# raijel_sim_v1.net
KiCad netlist of a schematic drawn in Altium Designer
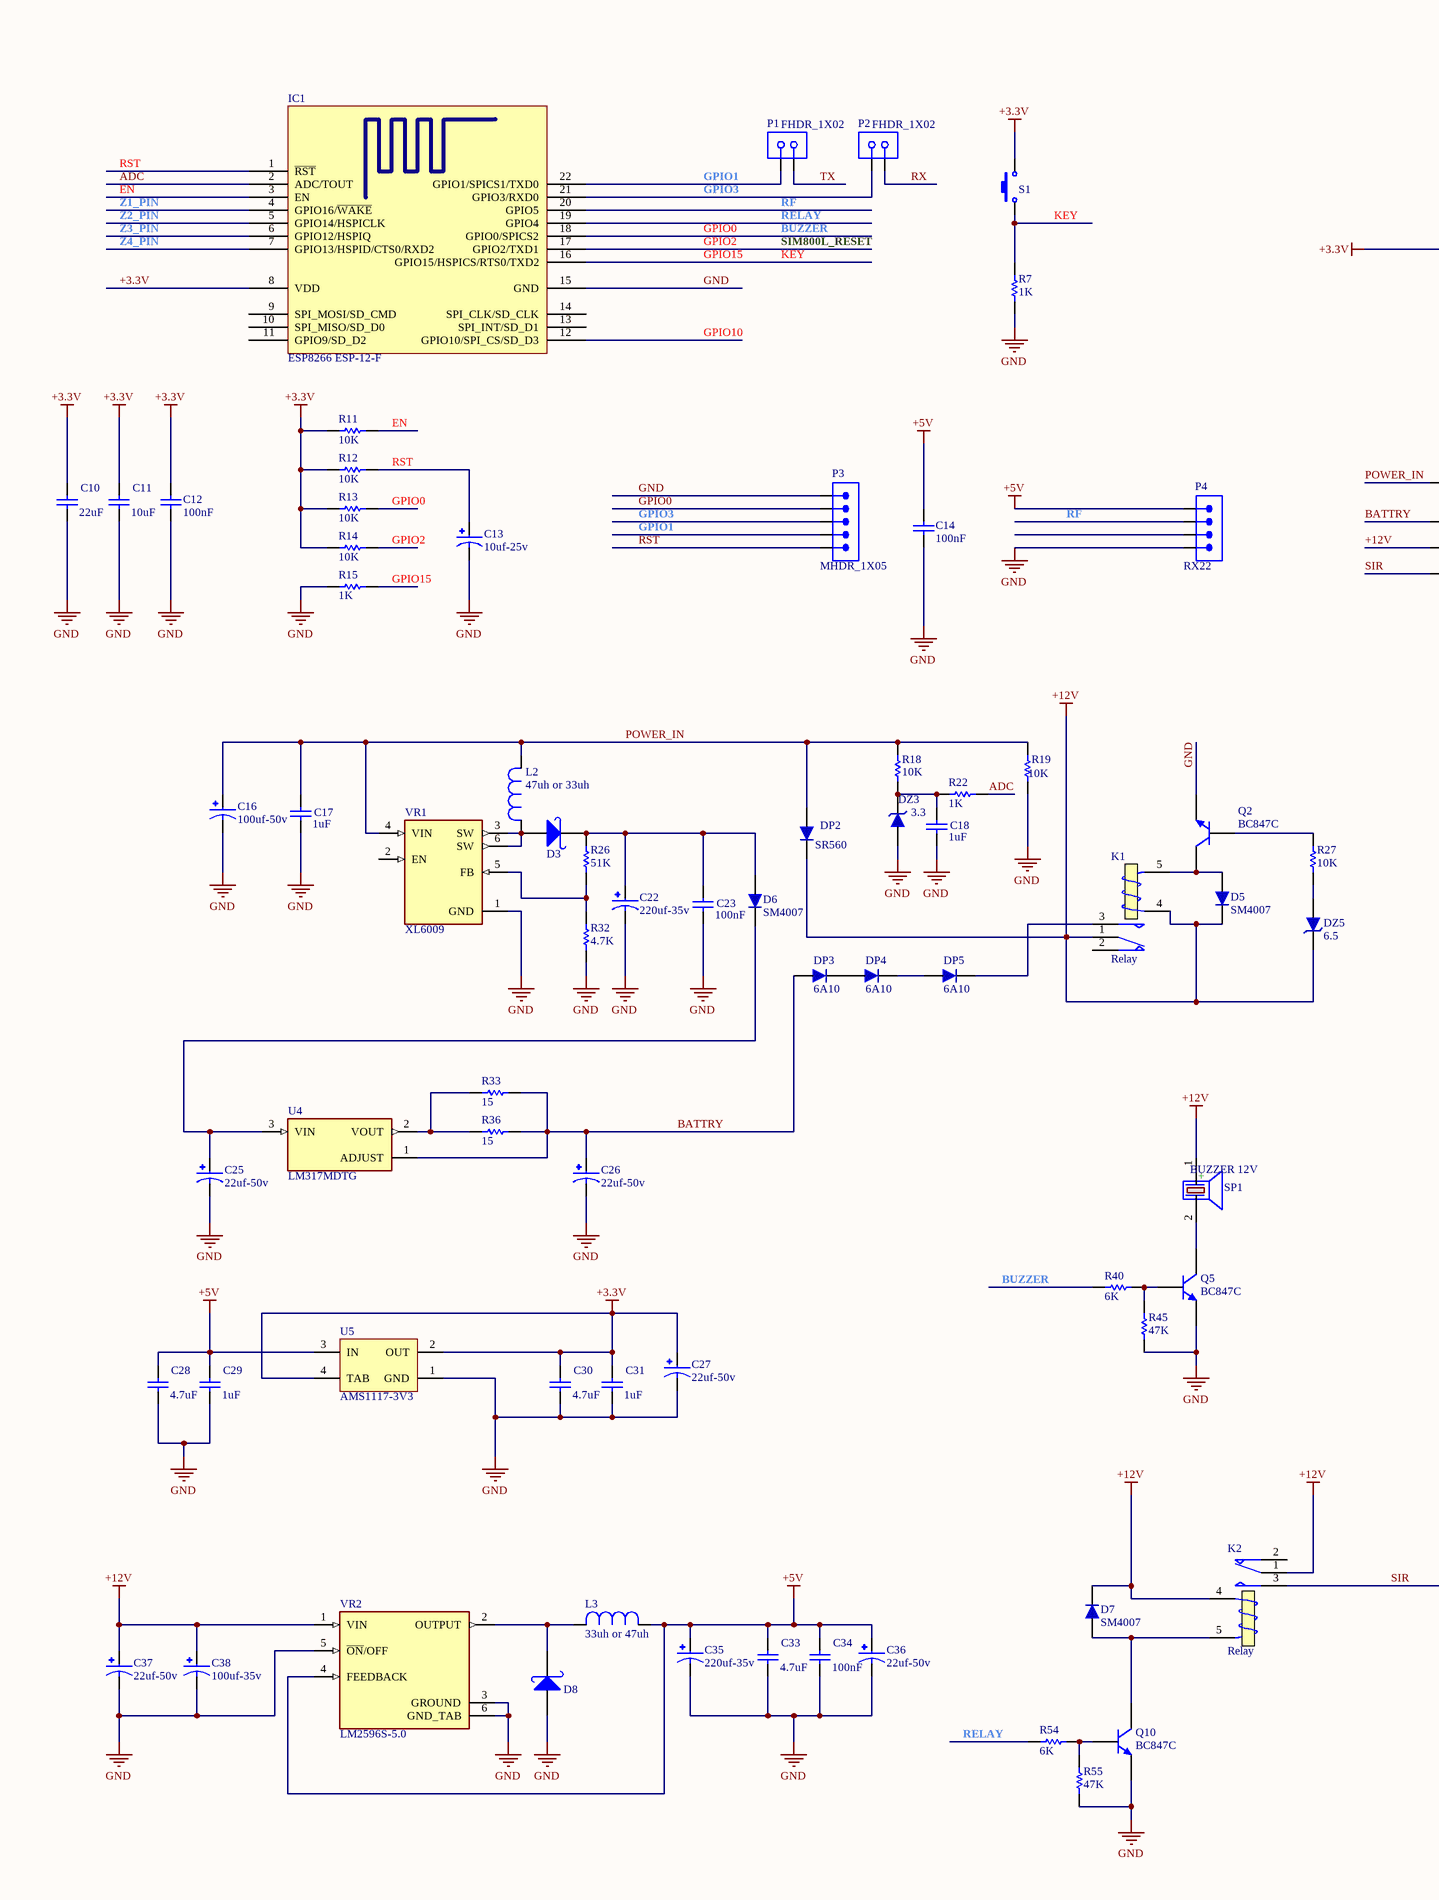
[diagram p0: raijel_sim_v1.SchDoc, left]
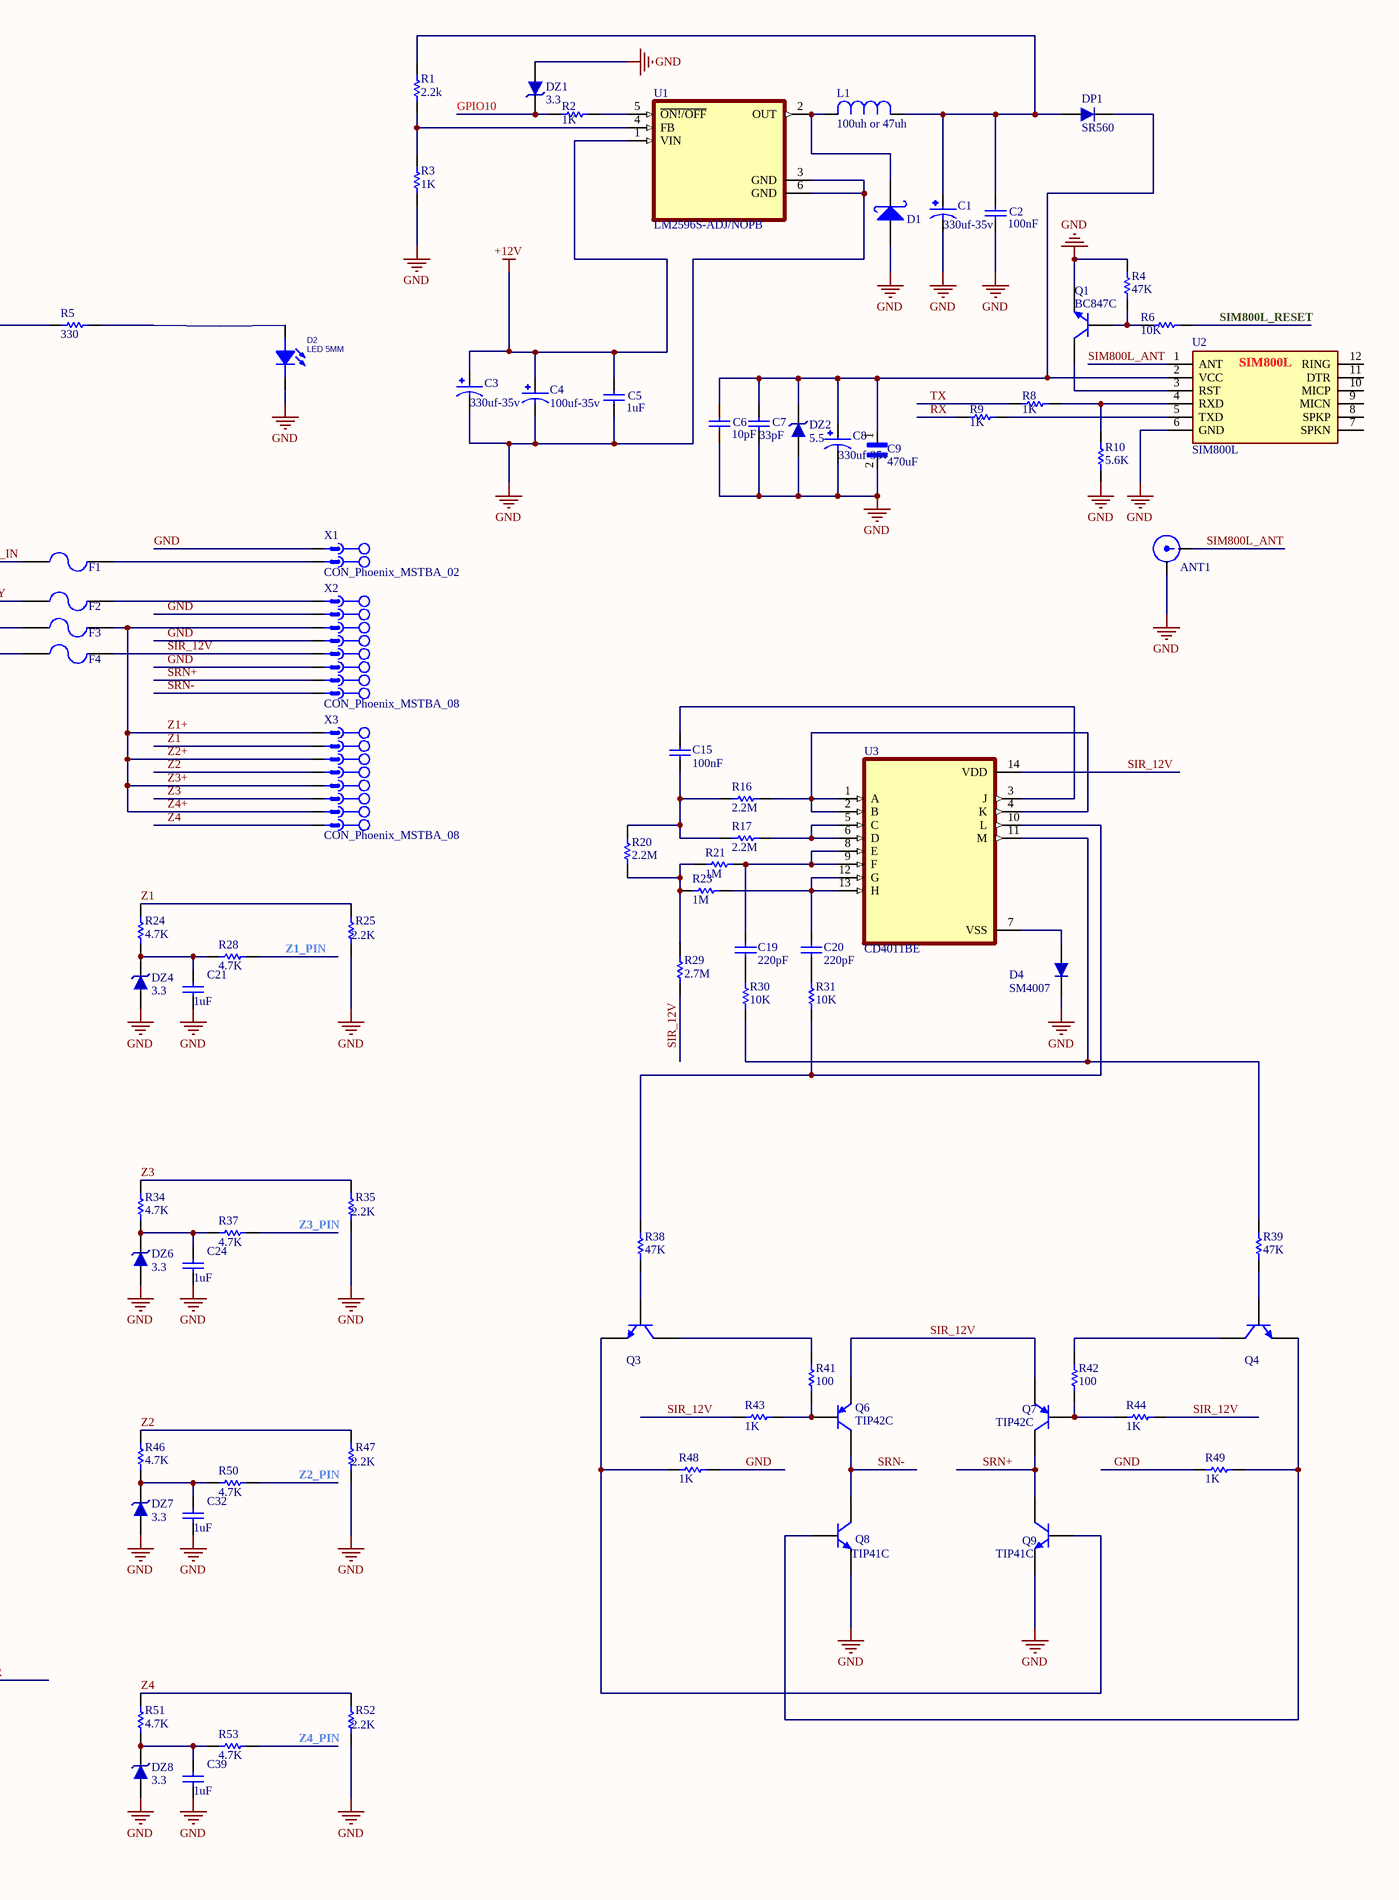
[diagram p1: raijel_sim_v1.SchDoc, right]

(export (version "E")
  (design (tool "Eeschema 10.0.6"))
  (components
    (comp (ref "ANT1")
      (value "Antenna")
      (footprint "SMA")
      (fields (field (name "DESIGNER") "Ali Hafizi"))
      (libsource (lib "Altium") (part "ANT SMA"))
    )
    (comp (ref "C1")
      (value "330uf-35v")
      (footprint "CAP_EEEFP1V221AV")
      (description "CAP ALUM 220UF 20% 35V SMD")
      (fields (field (name "MF") "Panasonic Electronic Components") (field (name "MP") "EEE-FP1V221AV"))
      (libsource (lib "EEEFP1V221AV-220-35v") (part "EEEFP1V221AV"))
    )
    (comp (ref "C2")
      (value "100nF")
      (footprint "CAP0805")
      (description "TOTAL CAPACITOR SMD PACK")
      (fields (field (name "DESIGNER") "Abbas Basereh"))
      (libsource (lib "Altium") (part "CAP SMD PACKAGE"))
    )
    (comp (ref "C3")
      (value "330uf-35v")
      (footprint "CAP_EEEFP1V221AV")
      (description "CAP ALUM 220UF 20% 35V SMD")
      (fields (field (name "MF") "Panasonic Electronic Components") (field (name "MP") "EEE-FP1V221AV"))
      (libsource (lib "EEEFP1V221AV-220-35v") (part "EEEFP1V221AV"))
    )
    (comp (ref "C4")
      (value "100uf-35v")
      (footprint "CAP_EEEFP1V221AV")
      (description "CAP ALUM 220UF 20% 35V SMD")
      (fields (field (name "MF") "Panasonic Electronic Components") (field (name "MP") "EEE-FP1V221AV"))
      (libsource (lib "EEEFP1V221AV-220-35v") (part "EEEFP1V221AV"))
    )
    (comp (ref "C5")
      (value "1uF")
      (footprint "CAP0805")
      (description "TOTAL CAPACITOR SMD PACK")
      (fields (field (name "DESIGNER") "Abbas Basereh"))
      (libsource (lib "Altium") (part "CAP SMD PACKAGE"))
    )
    (comp (ref "C6")
      (value "10pF")
      (footprint "CAP0805")
      (description "TOTAL CAPACITOR SMD PACK")
      (fields (field (name "DESIGNER") "Abbas Basereh"))
      (libsource (lib "Altium") (part "CAP SMD PACKAGE"))
    )
    (comp (ref "C7")
      (value "33pF")
      (footprint "CAP0805")
      (description "TOTAL CAPACITOR SMD PACK")
      (fields (field (name "DESIGNER") "Abbas Basereh"))
      (libsource (lib "Altium") (part "CAP SMD PACKAGE"))
    )
    (comp (ref "C8")
      (value "330uf-35v")
      (footprint "CAP_EEEFP1V221AV")
      (description "CAP ALUM 220UF 20% 35V SMD")
      (fields (field (name "MF") "Panasonic Electronic Components") (field (name "MP") "EEE-FP1V221AV"))
      (libsource (lib "EEEFP1V221AV-220-35v") (part "EEEFP1V221AV"))
    )
    (comp (ref "C9")
      (value "470uF")
      (footprint "CAPPM7343X310N")
      (description "TC 47uF 25V 10% Case D")
      (fields (field (name "MP") "TAJD476K025RNJ"))
      (libsource (lib "TAJD476K025RNJ") (part "TAJD476K025RNJ"))
    )
    (comp (ref "C10")
      (value "22uF")
      (footprint "CAP0805")
      (description "TOTAL CAPACITOR SMD PACK")
      (fields (field (name "DESIGNER") "Abbas Basereh"))
      (libsource (lib "Altium") (part "CAP SMD PACKAGE"))
    )
    (comp (ref "C11")
      (value "10uF")
      (footprint "CAP0805")
      (description "TOTAL CAPACITOR SMD PACK")
      (fields (field (name "DESIGNER") "Abbas Basereh"))
      (libsource (lib "Altium") (part "CAP SMD PACKAGE"))
    )
    (comp (ref "C12")
      (value "100nF")
      (footprint "CAP0805")
      (description "TOTAL CAPACITOR SMD PACK")
      (fields (field (name "DESIGNER") "Abbas Basereh"))
      (libsource (lib "Altium") (part "CAP SMD PACKAGE"))
    )
    (comp (ref "C13")
      (value "10uf-25v")
      (footprint "CAP_EEEFN1H220UR")
      (description "CAP ALUM 22UF 20% 50V SMD")
      (fields (field (name "MF") "Panasonic Electronic Components") (field (name "MP") "EEE-FN1H220UR"))
      (libsource (lib "EEEFN1H220UR_22uf-50v") (part "EEEFN1H220UR"))
    )
    (comp (ref "C14")
      (value "100nF")
      (footprint "CAP0805")
      (description "TOTAL CAPACITOR SMD PACK")
      (fields (field (name "DESIGNER") "Abbas Basereh"))
      (libsource (lib "Altium") (part "CAP SMD PACKAGE"))
    )
    (comp (ref "C15")
      (value "100nF")
      (footprint "CAP Ceramic 5mm")
      (description "CAP Ceramic Total")
      (fields (field (name "DESIGNER") "Ali Hafizi"))
      (libsource (lib "Altium") (part "CAP CERAMIC TOTAL SIZE"))
    )
    (comp (ref "C16")
      (value "100uf-50v")
      (footprint "CAP_EEEFN1H101L")
      (description "CAP ALUM 100UF 20% 50V SMD")
      (fields (field (name "MP") "EEE-FN1H101L") (field (name "MF") "Panasonic Electronic Components"))
      (libsource (lib "EEEFN1H101L-100-50v") (part "EEEFN1H101L"))
    )
    (comp (ref "C17")
      (value "1uF")
      (footprint "CAP0805")
      (description "TOTAL CAPACITOR SMD PACK")
      (fields (field (name "DESIGNER") "Abbas Basereh"))
      (libsource (lib "Altium") (part "CAP SMD PACKAGE"))
    )
    (comp (ref "C18")
      (value "1uF")
      (footprint "CAP0805")
      (description "TOTAL CAPACITOR SMD PACK")
      (fields (field (name "DESIGNER") "Abbas Basereh"))
      (libsource (lib "Altium") (part "CAP SMD PACKAGE"))
    )
    (comp (ref "C19")
      (value "220pF")
      (footprint "CAP Ceramic 5mm")
      (description "CAP Ceramic Total")
      (fields (field (name "DESIGNER") "Ali Hafizi"))
      (libsource (lib "Altium") (part "CAP CERAMIC TOTAL SIZE"))
    )
    (comp (ref "C20")
      (value "220pF")
      (footprint "CAP Ceramic 5mm")
      (description "CAP Ceramic Total")
      (fields (field (name "DESIGNER") "Ali Hafizi"))
      (libsource (lib "Altium") (part "CAP CERAMIC TOTAL SIZE"))
    )
    (comp (ref "C21")
      (value "1uF")
      (footprint "CAP0805")
      (description "TOTAL CAPACITOR SMD PACK")
      (fields (field (name "DESIGNER") "Abbas Basereh"))
      (libsource (lib "Altium") (part "CAP SMD PACKAGE"))
    )
    (comp (ref "C22")
      (value "220uf-35v")
      (footprint "CAP_EEEFP1V221AV")
      (description "CAP ALUM 220UF 20% 35V SMD")
      (fields (field (name "MF") "Panasonic Electronic Components") (field (name "MP") "EEE-FP1V221AV"))
      (libsource (lib "EEEFP1V221AV-220-35v") (part "EEEFP1V221AV"))
    )
    (comp (ref "C23")
      (value "100nF")
      (footprint "CAP0805")
      (description "TOTAL CAPACITOR SMD PACK")
      (fields (field (name "DESIGNER") "Abbas Basereh"))
      (libsource (lib "Altium") (part "CAP SMD PACKAGE"))
    )
    (comp (ref "C24")
      (value "1uF")
      (footprint "CAP0805")
      (description "TOTAL CAPACITOR SMD PACK")
      (fields (field (name "DESIGNER") "Abbas Basereh"))
      (libsource (lib "Altium") (part "CAP SMD PACKAGE"))
    )
    (comp (ref "C25")
      (value "22uf-50v")
      (footprint "CAP_EEEFN1H220UR")
      (description "CAP ALUM 22UF 20% 50V SMD")
      (fields (field (name "MF") "Panasonic Electronic Components") (field (name "MP") "EEE-FN1H220UR"))
      (libsource (lib "EEEFN1H220UR_22uf-50v") (part "EEEFN1H220UR"))
    )
    (comp (ref "C26")
      (value "22uf-50v")
      (footprint "CAP_EEEFN1H220UR")
      (description "CAP ALUM 22UF 20% 50V SMD")
      (fields (field (name "MF") "Panasonic Electronic Components") (field (name "MP") "EEE-FN1H220UR"))
      (libsource (lib "EEEFN1H220UR_22uf-50v") (part "EEEFN1H220UR"))
    )
    (comp (ref "C27")
      (value "22uf-50v")
      (footprint "CAP_EEEFN1H220UR")
      (description "CAP ALUM 22UF 20% 50V SMD")
      (fields (field (name "MF") "Panasonic Electronic Components") (field (name "MP") "EEE-FN1H220UR"))
      (libsource (lib "EEEFN1H220UR_22uf-50v") (part "EEEFN1H220UR"))
    )
    (comp (ref "C28")
      (value "4.7uF")
      (footprint "CAP0805")
      (description "TOTAL CAPACITOR SMD PACK")
      (fields (field (name "DESIGNER") "Abbas Basereh"))
      (libsource (lib "Altium") (part "CAP SMD PACKAGE"))
    )
    (comp (ref "C29")
      (value "1uF")
      (footprint "CAP0805")
      (description "TOTAL CAPACITOR SMD PACK")
      (fields (field (name "DESIGNER") "Abbas Basereh"))
      (libsource (lib "Altium") (part "CAP SMD PACKAGE"))
    )
    (comp (ref "C30")
      (value "4.7uF")
      (footprint "CAP0805")
      (description "TOTAL CAPACITOR SMD PACK")
      (fields (field (name "DESIGNER") "Abbas Basereh"))
      (libsource (lib "Altium") (part "CAP SMD PACKAGE"))
    )
    (comp (ref "C31")
      (value "1uF")
      (footprint "CAP0805")
      (description "TOTAL CAPACITOR SMD PACK")
      (fields (field (name "DESIGNER") "Abbas Basereh"))
      (libsource (lib "Altium") (part "CAP SMD PACKAGE"))
    )
    (comp (ref "C32")
      (value "1uF")
      (footprint "CAP0805")
      (description "TOTAL CAPACITOR SMD PACK")
      (fields (field (name "DESIGNER") "Abbas Basereh"))
      (libsource (lib "Altium") (part "CAP SMD PACKAGE"))
    )
    (comp (ref "C33")
      (value "4.7uF")
      (footprint "CAP0805")
      (description "TOTAL CAPACITOR SMD PACK")
      (fields (field (name "DESIGNER") "Abbas Basereh"))
      (libsource (lib "Altium") (part "CAP SMD PACKAGE"))
    )
    (comp (ref "C34")
      (value "100nF")
      (footprint "CAP0805")
      (description "TOTAL CAPACITOR SMD PACK")
      (fields (field (name "DESIGNER") "Abbas Basereh"))
      (libsource (lib "Altium") (part "CAP SMD PACKAGE"))
    )
    (comp (ref "C35")
      (value "220uf-35v")
      (footprint "CAP_EEEFP1V221AV")
      (description "CAP ALUM 220UF 20% 35V SMD")
      (fields (field (name "MF") "Panasonic Electronic Components") (field (name "MP") "EEE-FP1V221AV"))
      (libsource (lib "EEEFP1V221AV-220-35v") (part "EEEFP1V221AV"))
    )
    (comp (ref "C36")
      (value "22uf-50v")
      (footprint "CAP_EEEFN1H220UR")
      (description "CAP ALUM 22UF 20% 50V SMD")
      (fields (field (name "MF") "Panasonic Electronic Components") (field (name "MP") "EEE-FN1H220UR"))
      (libsource (lib "EEEFN1H220UR_22uf-50v") (part "EEEFN1H220UR"))
    )
    (comp (ref "C37")
      (value "22uf-50v")
      (footprint "CAP_EEEFN1H220UR")
      (description "CAP ALUM 22UF 20% 50V SMD")
      (fields (field (name "MF") "Panasonic Electronic Components") (field (name "MP") "EEE-FN1H220UR"))
      (libsource (lib "EEEFN1H220UR_22uf-50v") (part "EEEFN1H220UR"))
    )
    (comp (ref "C38")
      (value "100uf-35v")
      (footprint "CAP_EEEFP1V221AV")
      (description "CAP ALUM 220UF 20% 35V SMD")
      (fields (field (name "MF") "Panasonic Electronic Components") (field (name "MP") "EEE-FP1V221AV"))
      (libsource (lib "EEEFP1V221AV-220-35v") (part "EEEFP1V221AV"))
    )
    (comp (ref "C39")
      (value "1uF")
      (footprint "CAP0805")
      (description "TOTAL CAPACITOR SMD PACK")
      (fields (field (name "DESIGNER") "Abbas Basereh"))
      (libsource (lib "Altium") (part "CAP SMD PACKAGE"))
    )
    (comp (ref "D1")
      (value "1n5822")
      (footprint "DO-214AB(SMC)")
      (description "Schottky Rectifiers")
      (fields
        (field (name "MANUFACTURER") "ON Semiconductor/Fairchild")
        (field (name "DESIGNER") "Abbas Basereh")
      )
      (libsource (lib "Altium") (part "1N5822 SMD"))
    )
    (comp (ref "D2")
      (value "LED 5MM")
      (footprint "LED5MM_GRN")
      (description "Light Emitting Diode")
      (fields (field (name "DESIGNER") "Abbas Basereh"))
      (libsource (lib "Altium") (part "LED 5MM"))
    )
    (comp (ref "D3")
      (value "1n5822")
      (footprint "DO-214AB(SMC)")
      (description "Schottky Rectifiers")
      (fields
        (field (name "MANUFACTURER") "ON Semiconductor/Fairchild")
        (field (name "DESIGNER") "Abbas Basereh")
      )
      (libsource (lib "Altium") (part "1N5822 SMD"))
    )
    (comp (ref "D4")
      (value "SM4007")
      (footprint "DIODE SMD")
      (description "Diode SMD Pakage")
      (libsource (lib "Altium") (part "Diode SMD Package"))
    )
    (comp (ref "D5")
      (value "SM4007")
      (footprint "DIODE SMD")
      (description "Diode SMD Pakage")
      (libsource (lib "Altium") (part "Diode SMD Package"))
    )
    (comp (ref "D6")
      (value "SM4007")
      (footprint "DIODE SMD")
      (description "Diode SMD Pakage")
      (libsource (lib "Altium") (part "Diode SMD Package"))
    )
    (comp (ref "D7")
      (value "SM4007")
      (footprint "DIODE SMD")
      (description "Diode SMD Pakage")
      (libsource (lib "Altium") (part "Diode SMD Package"))
    )
    (comp (ref "D8")
      (value "1n5822")
      (footprint "DO-214AB(SMC)")
      (description "Schottky Rectifiers")
      (fields
        (field (name "MANUFACTURER") "ON Semiconductor/Fairchild")
        (field (name "DESIGNER") "Abbas Basereh")
      )
      (libsource (lib "Altium") (part "1N5822 SMD"))
    )
    (comp (ref "DP1")
      (value "SR560")
      (footprint "DO-201AD - vertical")
      (description "General Semiconductor. Revision 3A 1000V Silicon Rectifier")
      (fields (field (name "DESIGNER") "Abbas Basereh"))
      (libsource (lib "General 1") (part "1N5408 3A 1000V"))
    )
    (comp (ref "DP2")
      (value "SR560")
      (footprint "DO-201AD - vertical")
      (description "General Semiconductor. Revision 3A 1000V Silicon Rectifier")
      (fields (field (name "DESIGNER") "Abbas Basereh"))
      (libsource (lib "General 1") (part "1N5408 3A 1000V"))
    )
    (comp (ref "DP3")
      (value "6A10")
      (footprint "DO-201AD - vertical")
      (description "General Semiconductor. Revision 3A 1000V Silicon Rectifier")
      (fields (field (name "DESIGNER") "Abbas Basereh"))
      (libsource (lib "General 1") (part "1N5408 3A 1000V"))
    )
    (comp (ref "DP4")
      (value "6A10")
      (footprint "DO-201AD - vertical")
      (description "General Semiconductor. Revision 3A 1000V Silicon Rectifier")
      (fields (field (name "DESIGNER") "Abbas Basereh"))
      (libsource (lib "General 1") (part "1N5408 3A 1000V"))
    )
    (comp (ref "DP5")
      (value "6A10")
      (footprint "DO-201AD - vertical")
      (description "General Semiconductor. Revision 3A 1000V Silicon Rectifier")
      (fields (field (name "DESIGNER") "Abbas Basereh"))
      (libsource (lib "General 1") (part "1N5408 3A 1000V"))
    )
    (comp (ref "DZ1")
      (value "3.3")
      (footprint "SOD80, LL-34")
      (description "DIODE ZENER GENERAL")
      (fields (field (name "PUBLISHER") "Abbas Basereh"))
      (libsource (lib "Altium") (part "ZENER GENERAL DIODE"))
    )
    (comp (ref "DZ2")
      (value "5.5")
      (footprint "SOD80, LL-34")
      (description "DIODE ZENER GENERAL")
      (fields (field (name "PUBLISHER") "Abbas Basereh"))
      (libsource (lib "Altium") (part "ZENER GENERAL DIODE"))
    )
    (comp (ref "DZ3")
      (value "3.3")
      (footprint "SOD80, LL-34")
      (description "DIODE ZENER GENERAL")
      (fields (field (name "PUBLISHER") "Abbas Basereh"))
      (libsource (lib "Altium") (part "ZENER GENERAL DIODE"))
    )
    (comp (ref "DZ4")
      (value "3.3")
      (footprint "SOD80, LL-34")
      (description "DIODE ZENER GENERAL")
      (fields (field (name "PUBLISHER") "Abbas Basereh"))
      (libsource (lib "Altium") (part "ZENER GENERAL DIODE"))
    )
    (comp (ref "DZ5")
      (value "6.5")
      (footprint "SOD80, LL-34")
      (description "DIODE ZENER GENERAL")
      (fields (field (name "PUBLISHER") "Abbas Basereh"))
      (libsource (lib "Altium") (part "ZENER GENERAL DIODE"))
    )
    (comp (ref "DZ6")
      (value "3.3")
      (footprint "SOD80, LL-34")
      (description "DIODE ZENER GENERAL")
      (fields (field (name "PUBLISHER") "Abbas Basereh"))
      (libsource (lib "Altium") (part "ZENER GENERAL DIODE"))
    )
    (comp (ref "DZ7")
      (value "3.3")
      (footprint "SOD80, LL-34")
      (description "DIODE ZENER GENERAL")
      (fields (field (name "PUBLISHER") "Abbas Basereh"))
      (libsource (lib "Altium") (part "ZENER GENERAL DIODE"))
    )
    (comp (ref "DZ8")
      (value "3.3")
      (footprint "SOD80, LL-34")
      (description "DIODE ZENER GENERAL")
      (fields (field (name "PUBLISHER") "Abbas Basereh"))
      (libsource (lib "Altium") (part "ZENER GENERAL DIODE"))
    )
    (comp (ref "F1")
      (value "F=1.0 A")
      (footprint "Fuse 5x20 With holder pin")
      (description "Fuses 5x20")
      (fields (field (name "DESIGNER") "Abbas Basereh"))
      (libsource (lib "Altium") (part "Fuse 5x20 with holdeer pins"))
    )
    (comp (ref "F2")
      (value "F=1.0 A")
      (footprint "Fuse 5x20 With holder pin")
      (description "Fuses 5x20")
      (fields (field (name "DESIGNER") "Abbas Basereh"))
      (libsource (lib "Altium") (part "Fuse 5x20 with holdeer pins"))
    )
    (comp (ref "F3")
      (value "F=1.0 A")
      (footprint "Fuse 5x20 With holder pin")
      (description "Fuses 5x20")
      (fields (field (name "DESIGNER") "Abbas Basereh"))
      (libsource (lib "Altium") (part "Fuse 5x20 with holdeer pins"))
    )
    (comp (ref "F4")
      (value "F=1.0 A")
      (footprint "Fuse 5x20 With holder pin")
      (description "Fuses 5x20")
      (fields (field (name "DESIGNER") "Abbas Basereh"))
      (libsource (lib "Altium") (part "Fuse 5x20 with holdeer pins"))
    )
    (comp (ref "IC1")
      (value "ESP8266 ESP-12-F")
      (footprint "ESP8266-12E")
      (description "ESP8266 ESP-12-E")
      (libsource (lib "ESP8266") (part "ESP8266 ESP-12-E"))
    )
    (comp (ref "K1")
      (value "Relay")
      (footprint "Relay 15.40x12.10x13.10")
      (description "Relay_SPDT POWER NEEDLE")
      (fields (field (name "DESIGNER") "Ali Hafizi"))
      (libsource (lib "Altium") (part "RELAY General"))
    )
    (comp (ref "K2")
      (value "Relay")
      (footprint "Relay 15.40x12.10x13.10")
      (description "Relay_SPDT POWER NEEDLE")
      (fields (field (name "DESIGNER") "Ali Hafizi"))
      (libsource (lib "") (part "RELAY General_1"))
    )
    (comp (ref "L1")
      (value "100uh or 47uh")
      (footprint "IND_CDRH127/LDNP-470MC_SUM")
      (description "47ÂµH Shielded Inductor 3.25A 78mOhm Max Nonstandard")
      (fields (field (name "DIGI-KEY_PART_NUMBER") "308-1339-1-ND") (field (name "MF") "Sumida America"))
      (libsource (lib "CDRH127_LDNP-470MC-47uh") (part "CDRH127/LDNP-470MC"))
    )
    (comp (ref "L2")
      (value "47uh or 33uh")
      (footprint "IND_CDRH127/LDNP-470MC_SUM")
      (description "47ÂµH Shielded Inductor 3.25A 78mOhm Max Nonstandard")
      (fields (field (name "DIGI-KEY_PART_NUMBER") "308-1339-1-ND") (field (name "MF") "Sumida America"))
      (libsource (lib "CDRH127_LDNP-470MC-47uh") (part "CDRH127/LDNP-470MC"))
    )
    (comp (ref "L3")
      (value "33uh or 47uh")
      (footprint "IND_CDRH127/LDNP-470MC_SUM")
      (description "47ÂµH Shielded Inductor 3.25A 78mOhm Max Nonstandard")
      (fields (field (name "DIGI-KEY_PART_NUMBER") "308-1339-1-ND") (field (name "MF") "Sumida America"))
      (libsource (lib "CDRH127_LDNP-470MC-47uh") (part "CDRH127/LDNP-470MC"))
    )
    (comp (ref "P1")
      (value "FHDR_1X02")
      (footprint "FHDR1X02-254P")
      (description "Female Header 1X02")
      (libsource (lib "Sockets And Connectors") (part "FHDR_1X02"))
    )
    (comp (ref "P2")
      (value "FHDR_1X02")
      (footprint "FHDR1X02-254P")
      (description "Female Header 1X02")
      (libsource (lib "Sockets And Connectors") (part "FHDR_1X02"))
    )
    (comp (ref "P3")
      (value "MHDR_1X05")
      (footprint "MHDR1X05-254P")
      (description "Male Header 1X05")
      (libsource (lib "Sockets And Connectors") (part "MHDR_1X05"))
    )
    (comp (ref "P4")
      (value "RX22")
      (footprint "MHDR1X04-254P")
      (description "Male Header 1X04")
      (libsource (lib "Sockets And Connectors") (part "MHDR_1X04"))
    )
    (comp (ref "Q1")
      (value "BC847C")
      (footprint "SOT23_N")
      (description "NPN General-purpose Transistor")
      (fields (field (name "PUBLISHER") "Abbas Basereh"))
      (libsource (lib "General 1") (part "BC847C"))
    )
    (comp (ref "Q2")
      (value "BC847C")
      (footprint "SOT23_N")
      (description "NPN General-purpose Transistor")
      (fields (field (name "PUBLISHER") "Abbas Basereh"))
      (libsource (lib "General 1") (part "BC847C"))
    )
    (comp (ref "Q3")
      (value "BC547")
      (footprint "TO-92 BENT")
      (description "NPN General-purpose Transistor")
      (fields (field (name "DESIGNER") "Abbas Basereh"))
      (libsource (lib "Altium") (part "BC547"))
    )
    (comp (ref "Q4")
      (value "BC547")
      (footprint "TO-92 BENT")
      (description "NPN General-purpose Transistor")
      (fields (field (name "DESIGNER") "Abbas Basereh"))
      (libsource (lib "Altium") (part "BC547"))
    )
    (comp (ref "Q5")
      (value "BC847C")
      (footprint "SOT23_N")
      (description "NPN General-purpose Transistor")
      (fields (field (name "PUBLISHER") "Abbas Basereh"))
      (libsource (lib "General 1") (part "BC847C"))
    )
    (comp (ref "Q6")
      (value "TIP42C")
      (footprint "TO-220 AB")
      (description "PNP  power transistor")
      (fields (field (name "MANUFACTURER") "STMicroelectronics") (field (name "DESIGNER") "Abbas Basereh"))
      (libsource (lib "Altium") (part "TIP42C"))
    )
    (comp (ref "Q7")
      (value "TIP42C")
      (footprint "TO-220 AB")
      (description "PNP  power transistor")
      (fields (field (name "MANUFACTURER") "STMicroelectronics") (field (name "DESIGNER") "Abbas Basereh"))
      (libsource (lib "Altium") (part "TIP42C"))
    )
    (comp (ref "Q8")
      (value "TIP41C")
      (footprint "TO-220 AB")
      (description "NPN  power transistor")
      (fields (field (name "MANUFACTURER") "STMicroelectronics") (field (name "DESIGNER") "Abbas Basereh"))
      (libsource (lib "Altium") (part "TIP41C"))
    )
    (comp (ref "Q9")
      (value "TIP41C")
      (footprint "TO-220 AB")
      (description "NPN  power transistor")
      (fields (field (name "MANUFACTURER") "STMicroelectronics") (field (name "DESIGNER") "Abbas Basereh"))
      (libsource (lib "Altium") (part "TIP41C"))
    )
    (comp (ref "Q10")
      (value "BC847C")
      (footprint "SOT23_N")
      (description "NPN General-purpose Transistor")
      (fields (field (name "PUBLISHER") "Abbas Basereh"))
      (libsource (lib "General 1") (part "BC847C"))
    )
    (comp (ref "R1")
      (value "2.2k")
      (footprint "RES0805")
      (description "TOTAL SMD RESISTOR PACK")
      (fields (field (name "DESIGNER") "Abbas Basereh"))
      (libsource (lib "Altium") (part "RES SMD PACKAGE"))
    )
    (comp (ref "R2")
      (value "1K")
      (footprint "RES0805")
      (description "TOTAL SMD RESISTOR PACK")
      (fields (field (name "DESIGNER") "Abbas Basereh"))
      (libsource (lib "Altium") (part "RES SMD PACKAGE"))
    )
    (comp (ref "R3")
      (value "1K")
      (footprint "RES0805_(2012X06L)")
      (description "TOTAL SMD RESISTOR PACK")
      (fields (field (name "DESIGNER") "Abbas Basereh"))
      (libsource (lib "Altium") (part "RES SMD PACKAGE"))
    )
    (comp (ref "R4")
      (value "47K")
      (footprint "RES0805")
      (description "TOTAL SMD RESISTOR PACK")
      (fields (field (name "DESIGNER") "Abbas Basereh"))
      (libsource (lib "Altium") (part "RES SMD PACKAGE"))
    )
    (comp (ref "R5")
      (value "330")
      (footprint "RES0805")
      (description "TOTAL SMD RESISTOR PACK")
      (fields (field (name "DESIGNER") "Abbas Basereh"))
      (libsource (lib "Altium") (part "RES SMD PACKAGE"))
    )
    (comp (ref "R6")
      (value "10K")
      (footprint "RES0805")
      (description "TOTAL SMD RESISTOR PACK")
      (fields (field (name "DESIGNER") "Abbas Basereh"))
      (libsource (lib "Altium") (part "RES SMD PACKAGE"))
    )
    (comp (ref "R7")
      (value "1K")
      (footprint "RES0805")
      (description "TOTAL SMD RESISTOR PACK")
      (fields (field (name "DESIGNER") "Abbas Basereh"))
      (libsource (lib "Altium") (part "RES SMD PACKAGE"))
    )
    (comp (ref "R8")
      (value "1K")
      (footprint "RES0805")
      (description "TOTAL SMD RESISTOR PACK")
      (fields (field (name "DESIGNER") "Abbas Basereh"))
      (libsource (lib "Altium") (part "RES SMD PACKAGE"))
    )
    (comp (ref "R9")
      (value "1K")
      (footprint "RES0805")
      (description "TOTAL SMD RESISTOR PACK")
      (fields (field (name "DESIGNER") "Abbas Basereh"))
      (libsource (lib "Altium") (part "RES SMD PACKAGE"))
    )
    (comp (ref "R10")
      (value "5.6K")
      (footprint "RES0805")
      (description "TOTAL SMD RESISTOR PACK")
      (fields (field (name "DESIGNER") "Abbas Basereh"))
      (libsource (lib "Altium") (part "RES SMD PACKAGE"))
    )
    (comp (ref "R11")
      (value "10K")
      (footprint "RES0805")
      (description "TOTAL SMD RESISTOR PACK")
      (fields (field (name "DESIGNER") "Abbas Basereh"))
      (libsource (lib "Altium") (part "RES SMD PACKAGE"))
    )
    (comp (ref "R12")
      (value "10K")
      (footprint "RES0805")
      (description "TOTAL SMD RESISTOR PACK")
      (fields (field (name "DESIGNER") "Abbas Basereh"))
      (libsource (lib "Altium") (part "RES SMD PACKAGE"))
    )
    (comp (ref "R13")
      (value "10K")
      (footprint "RES0805")
      (description "TOTAL SMD RESISTOR PACK")
      (fields (field (name "DESIGNER") "Abbas Basereh"))
      (libsource (lib "Altium") (part "RES SMD PACKAGE"))
    )
    (comp (ref "R14")
      (value "10K")
      (footprint "RES0805")
      (description "TOTAL SMD RESISTOR PACK")
      (fields (field (name "DESIGNER") "Abbas Basereh"))
      (libsource (lib "Altium") (part "RES SMD PACKAGE"))
    )
    (comp (ref "R15")
      (value "1K")
      (footprint "RES0805")
      (description "TOTAL SMD RESISTOR PACK")
      (fields (field (name "DESIGNER") "Abbas Basereh"))
      (libsource (lib "Altium") (part "RES SMD PACKAGE"))
    )
    (comp (ref "R16")
      (value "2.2M")
      (footprint "RES0805")
      (description "TOTAL SMD RESISTOR PACK")
      (fields (field (name "DESIGNER") "Abbas Basereh"))
      (libsource (lib "Altium") (part "RES SMD PACKAGE"))
    )
    (comp (ref "R17")
      (value "2.2M")
      (footprint "RES0805")
      (description "TOTAL SMD RESISTOR PACK")
      (fields (field (name "DESIGNER") "Abbas Basereh"))
      (libsource (lib "Altium") (part "RES SMD PACKAGE"))
    )
    (comp (ref "R18")
      (value "10K")
      (footprint "RES0805")
      (description "TOTAL SMD RESISTOR PACK")
      (fields (field (name "DESIGNER") "Abbas Basereh"))
      (libsource (lib "Altium") (part "RES SMD PACKAGE"))
    )
    (comp (ref "R19")
      (value "10K")
      (footprint "RES0805")
      (description "TOTAL SMD RESISTOR PACK")
      (fields (field (name "DESIGNER") "Abbas Basereh"))
      (libsource (lib "Altium") (part "RES SMD PACKAGE"))
    )
    (comp (ref "R20")
      (value "2.2M")
      (footprint "RES0805")
      (description "TOTAL SMD RESISTOR PACK")
      (fields (field (name "DESIGNER") "Abbas Basereh"))
      (libsource (lib "Altium") (part "RES SMD PACKAGE"))
    )
    (comp (ref "R21")
      (value "1M")
      (footprint "RES0805")
      (description "TOTAL SMD RESISTOR PACK")
      (fields (field (name "DESIGNER") "Abbas Basereh"))
      (libsource (lib "Altium") (part "RES SMD PACKAGE"))
    )
    (comp (ref "R22")
      (value "1K")
      (footprint "RES0805")
      (description "TOTAL SMD RESISTOR PACK")
      (fields (field (name "DESIGNER") "Abbas Basereh"))
      (libsource (lib "Altium") (part "RES SMD PACKAGE"))
    )
    (comp (ref "R23")
      (value "1M")
      (footprint "RES0805")
      (description "TOTAL SMD RESISTOR PACK")
      (fields (field (name "DESIGNER") "Abbas Basereh"))
      (libsource (lib "Altium") (part "RES SMD PACKAGE"))
    )
    (comp (ref "R24")
      (value "4.7K")
      (footprint "RES1206")
      (description "TOTAL SMD RESISTOR PACK")
      (fields (field (name "DESIGNER") "Abbas Basereh"))
      (libsource (lib "Altium") (part "RES SMD PACKAGE"))
    )
    (comp (ref "R25")
      (value "2.2K")
      (footprint "RES1206")
      (description "TOTAL SMD RESISTOR PACK")
      (fields (field (name "DESIGNER") "Abbas Basereh"))
      (libsource (lib "Altium") (part "RES SMD PACKAGE"))
    )
    (comp (ref "R26")
      (value "51K")
      (footprint "RES0805_(2012X06L)")
      (description "TOTAL SMD RESISTOR PACK")
      (fields (field (name "DESIGNER") "Abbas Basereh"))
      (libsource (lib "Altium") (part "RES SMD PACKAGE"))
    )
    (comp (ref "R27")
      (value "10K")
      (footprint "RES0805")
      (description "TOTAL SMD RESISTOR PACK")
      (fields (field (name "DESIGNER") "Abbas Basereh"))
      (libsource (lib "Altium") (part "RES SMD PACKAGE"))
    )
    (comp (ref "R28")
      (value "4.7K")
      (footprint "RES0805")
      (description "TOTAL SMD RESISTOR PACK")
      (fields (field (name "DESIGNER") "Abbas Basereh"))
      (libsource (lib "Altium") (part "RES SMD PACKAGE"))
    )
    (comp (ref "R29")
      (value "2.7M")
      (footprint "RES0805")
      (description "TOTAL SMD RESISTOR PACK")
      (fields (field (name "DESIGNER") "Abbas Basereh"))
      (libsource (lib "Altium") (part "RES SMD PACKAGE"))
    )
    (comp (ref "R30")
      (value "10K")
      (footprint "RES0805")
      (description "TOTAL SMD RESISTOR PACK")
      (fields (field (name "DESIGNER") "Abbas Basereh"))
      (libsource (lib "Altium") (part "RES SMD PACKAGE"))
    )
    (comp (ref "R31")
      (value "10K")
      (footprint "RES0805")
      (description "TOTAL SMD RESISTOR PACK")
      (fields (field (name "DESIGNER") "Abbas Basereh"))
      (libsource (lib "Altium") (part "RES SMD PACKAGE"))
    )
    (comp (ref "R32")
      (value "4.7K")
      (footprint "RES0805_(2012X06L)")
      (description "TOTAL SMD RESISTOR PACK")
      (fields (field (name "DESIGNER") "Abbas Basereh"))
      (libsource (lib "Altium") (part "RES SMD PACKAGE"))
    )
    (comp (ref "R33")
      (value "15")
      (footprint "Axial 0_5W 5_0mm")
      (description "RES Axial 0.5W")
      (fields (field (name "DESIGNER") "Abbas Basereh"))
      (libsource (lib "General 1") (part "RES Axial 0.5W"))
    )
    (comp (ref "R34")
      (value "4.7K")
      (footprint "RES1206")
      (description "TOTAL SMD RESISTOR PACK")
      (fields (field (name "DESIGNER") "Abbas Basereh"))
      (libsource (lib "Altium") (part "RES SMD PACKAGE"))
    )
    (comp (ref "R35")
      (value "2.2K")
      (footprint "RES1206")
      (description "TOTAL SMD RESISTOR PACK")
      (fields (field (name "DESIGNER") "Abbas Basereh"))
      (libsource (lib "Altium") (part "RES SMD PACKAGE"))
    )
    (comp (ref "R36")
      (value "15")
      (footprint "Axial 0_5W 5_0mm")
      (description "RES Axial 0.5W")
      (fields (field (name "DESIGNER") "Abbas Basereh"))
      (libsource (lib "General 1") (part "RES Axial 0.5W"))
    )
    (comp (ref "R37")
      (value "4.7K")
      (footprint "RES0805")
      (description "TOTAL SMD RESISTOR PACK")
      (fields (field (name "DESIGNER") "Abbas Basereh"))
      (libsource (lib "Altium") (part "RES SMD PACKAGE"))
    )
    (comp (ref "R38")
      (value "47K")
      (footprint "RES0805")
      (description "TOTAL SMD RESISTOR PACK")
      (fields (field (name "DESIGNER") "Abbas Basereh"))
      (libsource (lib "Altium") (part "RES SMD PACKAGE"))
    )
    (comp (ref "R39")
      (value "47K")
      (footprint "RES0805")
      (description "TOTAL SMD RESISTOR PACK")
      (fields (field (name "DESIGNER") "Abbas Basereh"))
      (libsource (lib "Altium") (part "RES SMD PACKAGE"))
    )
    (comp (ref "R40")
      (value "6K")
      (footprint "RES0805")
      (description "TOTAL SMD RESISTOR PACK")
      (fields (field (name "DESIGNER") "Abbas Basereh"))
      (libsource (lib "Altium") (part "RES SMD PACKAGE"))
    )
    (comp (ref "R41")
      (value "100")
      (footprint "Axial 0_5W 5_0mm")
      (description "RES Axial 0.5W")
      (fields (field (name "DESIGNER") "Abbas Basereh"))
      (libsource (lib "General 1") (part "RES Axial 0.5W"))
    )
    (comp (ref "R42")
      (value "100")
      (footprint "Axial 0_5W 5_0mm")
      (description "RES Axial 0.5W")
      (fields (field (name "DESIGNER") "Abbas Basereh"))
      (libsource (lib "General 1") (part "RES Axial 0.5W"))
    )
    (comp (ref "R43")
      (value "1K")
      (footprint "RES0805")
      (description "TOTAL SMD RESISTOR PACK")
      (fields (field (name "DESIGNER") "Abbas Basereh"))
      (libsource (lib "Altium") (part "RES SMD PACKAGE"))
    )
    (comp (ref "R44")
      (value "1K")
      (footprint "RES0805")
      (description "TOTAL SMD RESISTOR PACK")
      (fields (field (name "DESIGNER") "Abbas Basereh"))
      (libsource (lib "Altium") (part "RES SMD PACKAGE"))
    )
    (comp (ref "R45")
      (value "47K")
      (footprint "RES0805")
      (description "TOTAL SMD RESISTOR PACK")
      (fields (field (name "DESIGNER") "Abbas Basereh"))
      (libsource (lib "Altium") (part "RES SMD PACKAGE"))
    )
    (comp (ref "R46")
      (value "4.7K")
      (footprint "RES1206")
      (description "TOTAL SMD RESISTOR PACK")
      (fields (field (name "DESIGNER") "Abbas Basereh"))
      (libsource (lib "Altium") (part "RES SMD PACKAGE"))
    )
    (comp (ref "R47")
      (value "2.2K")
      (footprint "RES1206")
      (description "TOTAL SMD RESISTOR PACK")
      (fields (field (name "DESIGNER") "Abbas Basereh"))
      (libsource (lib "Altium") (part "RES SMD PACKAGE"))
    )
    (comp (ref "R48")
      (value "1K")
      (footprint "RES0805")
      (description "TOTAL SMD RESISTOR PACK")
      (fields (field (name "DESIGNER") "Abbas Basereh"))
      (libsource (lib "Altium") (part "RES SMD PACKAGE"))
    )
    (comp (ref "R49")
      (value "1K")
      (footprint "RES0805")
      (description "TOTAL SMD RESISTOR PACK")
      (fields (field (name "DESIGNER") "Abbas Basereh"))
      (libsource (lib "Altium") (part "RES SMD PACKAGE"))
    )
    (comp (ref "R50")
      (value "4.7K")
      (footprint "RES0805")
      (description "TOTAL SMD RESISTOR PACK")
      (fields (field (name "DESIGNER") "Abbas Basereh"))
      (libsource (lib "Altium") (part "RES SMD PACKAGE"))
    )
    (comp (ref "R51")
      (value "4.7K")
      (footprint "RES1206")
      (description "TOTAL SMD RESISTOR PACK")
      (fields (field (name "DESIGNER") "Abbas Basereh"))
      (libsource (lib "Altium") (part "RES SMD PACKAGE"))
    )
    (comp (ref "R52")
      (value "2.2K")
      (footprint "RES1206")
      (description "TOTAL SMD RESISTOR PACK")
      (fields (field (name "DESIGNER") "Abbas Basereh"))
      (libsource (lib "Altium") (part "RES SMD PACKAGE"))
    )
    (comp (ref "R53")
      (value "4.7K")
      (footprint "RES0805")
      (description "TOTAL SMD RESISTOR PACK")
      (fields (field (name "DESIGNER") "Abbas Basereh"))
      (libsource (lib "Altium") (part "RES SMD PACKAGE"))
    )
    (comp (ref "R54")
      (value "6K")
      (footprint "RES0805")
      (description "TOTAL SMD RESISTOR PACK")
      (fields (field (name "DESIGNER") "Abbas Basereh"))
      (libsource (lib "Altium") (part "RES SMD PACKAGE"))
    )
    (comp (ref "R55")
      (value "47K")
      (footprint "RES0805")
      (description "TOTAL SMD RESISTOR PACK")
      (fields (field (name "DESIGNER") "Abbas Basereh"))
      (libsource (lib "Altium") (part "RES SMD PACKAGE"))
    )
    (comp (ref "S1")
      (value "Switch PB")
      (footprint "Switch - Push to On")
      (description "Push Button Switch")
      (libsource (lib "Altium") (part "Switch PB"))
    )
    (comp (ref "SP1")
      (value "BUZZER 12V")
      (footprint "BUZZER 7.62mm DC")
      (description "PIEZO BUZZER ACTIVE")
      (fields (field (name "DESIGNER") "Abbas Basereh") (field (name "PUBLISHER") "Abbas Basereh"))
      (libsource (lib "Altium") (part "PIEZO BUZZER"))
    )
    (comp (ref "U1")
      (value "LM2596S-ADJ/NOPB")
      (footprint "VREG_LM2596S-ADJ/NOPB")
      (fields (field (name "MF") "Texas Instruments"))
      (libsource (lib "LM2596S-ADJ_NOPB") (part "LM2596S-ADJ/NOPB"))
    )
    (comp (ref "U2")
      (value "SIM800L")
      (footprint "SIM800L")
      (fields (field (name "PUBLISHER") "3DFootprint.ir"))
      (libsource (lib "SIM800L") (part "SIM800L"))
    )
    (comp (ref "U3")
      (value "CD4011BE")
      (footprint "DIP794W45P254L1969H508Q14")
      (libsource (lib "CD4011BE") (part "CD4011BE"))
    )
    (comp (ref "U4")
      (value "LM317MDTG")
      (footprint "VREG_LM317MDTG")
      (description "Linear Voltage Regulator IC Positive Adjustable 1 Output 500mA DPAK")
      (fields (field (name "DIGI-KEY_PART_NUMBER") "LM317MDTGOS-ND") (field (name "MF") "ON Semiconductor"))
      (libsource (lib "LM317MDTG") (part "LM317MDTG"))
    )
    (comp (ref "U5")
      (value "AMS1117-3V3")
      (footprint "SOT223")
      (description "x.x Volt, 800mA Low-Dropout Linear Regulator, 4-pin SOT-223")
      (fields (field (name "DESIGNER") "Ali Hafizi"))
      (libsource (lib "Altium") (part "AMS1117-x.x"))
    )
    (comp (ref "VR1")
      (value "XL6009")
      (footprint "DPAK170P1435X465-6N")
      (libsource (lib "XL6009") (part "XL6009"))
    )
    (comp (ref "VR2")
      (value "LM2596S-5.0")
      (footprint "TO170P1524X483-6N")
      (libsource (lib "LM2596S-5.0") (part "LM2596S-5.0"))
    )
    (comp (ref "X1")
      (value "CON_Phoenix_MSTBA_02")
      (footprint "CON_MSTBA02")
      (fields
        (field (name "MANUFACTURER") "PHOENIX CONTACT")
        (field (name "VOLTAGE") "320 V")
        (field (name "DESIGNER") "Eng. Saeid Jorablo")
        (field (name "PUBLISHER") "SJ UnLimited")
      )
      (libsource (lib "Sockets And Connectors") (part "CON_Phoenix_MSTBA_02"))
    )
    (comp (ref "X2")
      (value "CON_Phoenix_MSTBA_08")
      (footprint "CON_MSTBA08")
      (fields
        (field (name "MANUFACTURER") "PHOENIX CONTACT")
        (field (name "VOLTAGE") "320 V")
        (field (name "DESIGNER") "Eng. Saeid Jorablo")
        (field (name "PUBLISHER") "SJ UnLimited")
      )
      (libsource (lib "Sockets And Connectors") (part "CON_Phoenix_MSTBA_08"))
    )
    (comp (ref "X3")
      (value "CON_Phoenix_MSTBA_08")
      (footprint "CON_MSTBA08")
      (fields
        (field (name "MANUFACTURER") "PHOENIX CONTACT")
        (field (name "VOLTAGE") "320 V")
        (field (name "DESIGNER") "Eng. Saeid Jorablo")
        (field (name "PUBLISHER") "SJ UnLimited")
      )
      (libsource (lib "Sockets And Connectors") (part "CON_Phoenix_MSTBA_08"))
    )
  )
  (nets
    (net (code "1") (name "+3.3V") (class "Default")
      (node (ref "C10") (pin "2") (pinfunction "2_2") (pintype "passive"))
      (node (ref "C11") (pin "2") (pinfunction "2_2") (pintype "passive"))
      (node (ref "C12") (pin "2") (pinfunction "2_2") (pintype "passive"))
      (node (ref "C27") (pin "1") (pinfunction "1_1") (pintype "passive"))
      (node (ref "C30") (pin "2") (pinfunction "2_2") (pintype "passive"))
      (node (ref "C31") (pin "2") (pinfunction "2_2") (pintype "passive"))
      (node (ref "IC1") (pin "8") (pinfunction "VDD_8") (pintype "passive"))
      (node (ref "R11") (pin "2") (pinfunction "2_2") (pintype "passive"))
      (node (ref "R12") (pin "2") (pinfunction "2_2") (pintype "passive"))
      (node (ref "R13") (pin "2") (pinfunction "2_2") (pintype "passive"))
      (node (ref "R14") (pin "2") (pinfunction "2_2") (pintype "passive"))
      (node (ref "R5") (pin "1") (pinfunction "1_1") (pintype "passive"))
      (node (ref "S1") (pin "2") (pinfunction "2_2") (pintype "passive"))
      (node (ref "U5") (pin "2") (pinfunction "OUT_2") (pintype "power_in"))
      (node (ref "U5") (pin "4") (pinfunction "TAB_4") (pintype "power_in"))
    )
    (net (code "2") (name "+5V") (class "Default")
      (node (ref "C14") (pin "2") (pinfunction "2_2") (pintype "passive"))
      (node (ref "C28") (pin "2") (pinfunction "2_2") (pintype "passive"))
      (node (ref "C29") (pin "2") (pinfunction "2_2") (pintype "passive"))
      (node (ref "C33") (pin "2") (pinfunction "2_2") (pintype "passive"))
      (node (ref "C34") (pin "2") (pinfunction "2_2") (pintype "passive"))
      (node (ref "C35") (pin "1") (pinfunction "1_1") (pintype "passive"))
      (node (ref "C36") (pin "1") (pinfunction "1_1") (pintype "passive"))
      (node (ref "L3") (pin "1") (pinfunction "1_1") (pintype "passive"))
      (node (ref "P4") (pin "1") (pinfunction "1_1") (pintype "passive"))
      (node (ref "U5") (pin "3") (pinfunction "IN_3") (pintype "power_in"))
      (node (ref "VR2") (pin "4") (pinfunction "FEEDBACK_4") (pintype "input"))
    )
    (net (code "3") (name "+12V") (class "Default")
      (node (ref "C3") (pin "1") (pinfunction "1_1") (pintype "passive"))
      (node (ref "C37") (pin "1") (pinfunction "1_1") (pintype "passive"))
      (node (ref "C38") (pin "1") (pinfunction "1_1") (pintype "passive"))
      (node (ref "C4") (pin "1") (pinfunction "1_1") (pintype "passive"))
      (node (ref "C5") (pin "2") (pinfunction "2_2") (pintype "passive"))
      (node (ref "D5") (pin "2") (pintype "passive"))
      (node (ref "D7") (pin "2") (pintype "passive"))
      (node (ref "DP2") (pin "2") (pintype "passive"))
      (node (ref "DZ5") (pin "2") (pintype "passive"))
      (node (ref "F3") (pin "1") (pinfunction "1_1") (pintype "passive"))
      (node (ref "K1") (pin "1") (pinfunction "COM_1") (pintype "passive"))
      (node (ref "K1") (pin "4") (pinfunction "T1_4") (pintype "passive"))
      (node (ref "K2") (pin "1") (pinfunction "COM_1") (pintype "passive"))
      (node (ref "K2") (pin "4") (pinfunction "T1_4") (pintype "passive"))
      (node (ref "SP1") (pin "1") (pinfunction "+_1") (pintype "passive"))
      (node (ref "U1") (pin "1") (pinfunction "VIN_1") (pintype "input"))
      (node (ref "VR2") (pin "1") (pinfunction "VIN_1") (pintype "input"))
    )
    (net (code "4") (name "/ADC") (class "Default")
      (node (ref "IC1") (pin "2") (pinfunction "ADC/TOUT_2") (pintype "passive"))
      (node (ref "R22") (pin "1") (pinfunction "1_1") (pintype "passive"))
    )
    (net (code "5") (name "/BATTRY") (class "Default")
      (node (ref "C26") (pin "1") (pinfunction "1_1") (pintype "passive"))
      (node (ref "DP3") (pin "1") (pintype "passive"))
      (node (ref "F2") (pin "1") (pinfunction "1_1") (pintype "passive"))
      (node (ref "R33") (pin "2") (pinfunction "2_2") (pintype "passive"))
      (node (ref "R36") (pin "2") (pinfunction "2_2") (pintype "passive"))
      (node (ref "U4") (pin "1") (pinfunction "ADJUST_1") (pintype "passive"))
    )
    (net (code "6") (name "/BUZZER") (class "Default")
      (node (ref "IC1") (pin "18") (pinfunction "GPIO0/SPICS2_18") (pintype "passive"))
      (node (ref "P3") (pin "2") (pinfunction "2_2") (pintype "passive"))
      (node (ref "R13") (pin "1") (pinfunction "1_1") (pintype "passive"))
      (node (ref "R40") (pin "2") (pinfunction "2_2") (pintype "passive"))
    )
    (net (code "7") (name "/EN") (class "Default")
      (node (ref "IC1") (pin "3") (pinfunction "EN_3") (pintype "passive"))
      (node (ref "R11") (pin "1") (pinfunction "1_1") (pintype "passive"))
    )
    (net (code "8") (name "/GPIO1") (class "Default")
      (node (ref "IC1") (pin "22") (pinfunction "GPIO1/SPICS1/TXD0_22") (pintype "passive"))
      (node (ref "P1") (pin "1") (pinfunction "1_1") (pintype "passive"))
      (node (ref "P3") (pin "4") (pinfunction "4_4") (pintype "passive"))
    )
    (net (code "9") (name "/GPIO2") (class "Default")
      (node (ref "IC1") (pin "17") (pinfunction "GPIO2/TXD1_17") (pintype "passive"))
      (node (ref "R14") (pin "1") (pinfunction "1_1") (pintype "passive"))
      (node (ref "R6") (pin "2") (pinfunction "2_2") (pintype "passive"))
    )
    (net (code "10") (name "/GPIO3") (class "Default")
      (node (ref "IC1") (pin "21") (pinfunction "GPIO3/RXD0_21") (pintype "passive"))
      (node (ref "P2") (pin "1") (pinfunction "1_1") (pintype "passive"))
      (node (ref "P3") (pin "3") (pinfunction "3_3") (pintype "passive"))
    )
    (net (code "11") (name "/GPIO10") (class "Default")
      (node (ref "DZ1") (pin "2") (pintype "passive"))
      (node (ref "IC1") (pin "12") (pinfunction "GPIO10/SPI_CS/SD_D3_12") (pintype "passive"))
      (node (ref "R2") (pin "1") (pinfunction "1_1") (pintype "passive"))
    )
    (net (code "12") (name "/GPIO15") (class "Default")
      (node (ref "IC1") (pin "16") (pinfunction "GPIO15/HSPICS/RTS0/TXD2_16") (pintype "passive"))
      (node (ref "R15") (pin "1") (pinfunction "1_1") (pintype "passive"))
      (node (ref "R7") (pin "1") (pinfunction "1_1") (pintype "passive"))
      (node (ref "S1") (pin "1") (pinfunction "1_1") (pintype "passive"))
    )
    (net (code "13") (name "/POWER_IN") (class "Default")
      (node (ref "C16") (pin "1") (pinfunction "1_1") (pintype "passive"))
      (node (ref "C17") (pin "2") (pinfunction "2_2") (pintype "passive"))
      (node (ref "DP2") (pin "1") (pintype "passive"))
      (node (ref "F1") (pin "1") (pinfunction "1_1") (pintype "passive"))
      (node (ref "L2") (pin "1") (pinfunction "1_1") (pintype "passive"))
      (node (ref "R18") (pin "2") (pinfunction "2_2") (pintype "passive"))
      (node (ref "R19") (pin "1") (pinfunction "1_1") (pintype "passive"))
      (node (ref "VR1") (pin "4") (pinfunction "VIN_4") (pintype "input"))
    )
    (net (code "14") (name "/RELAY") (class "Default")
      (node (ref "IC1") (pin "19") (pinfunction "GPIO4_19") (pintype "passive"))
      (node (ref "R54") (pin "2") (pinfunction "2_2") (pintype "passive"))
    )
    (net (code "15") (name "/RF") (class "Default")
      (node (ref "IC1") (pin "20") (pinfunction "GPIO5_20") (pintype "passive"))
      (node (ref "P4") (pin "2") (pinfunction "2_2") (pintype "passive"))
    )
    (net (code "16") (name "/RST") (class "Default")
      (node (ref "C13") (pin "1") (pinfunction "1_1") (pintype "passive"))
      (node (ref "IC1") (pin "1") (pinfunction "~{RST}_1") (pintype "passive"))
      (node (ref "P3") (pin "5") (pinfunction "5_5") (pintype "passive"))
      (node (ref "R12") (pin "1") (pinfunction "1_1") (pintype "passive"))
    )
    (net (code "17") (name "/RX") (class "Default")
      (node (ref "P2") (pin "2") (pinfunction "2_2") (pintype "passive"))
      (node (ref "R9") (pin "1") (pinfunction "1_1") (pintype "passive"))
    )
    (net (code "18") (name "/SIM800L_ANT") (class "Default")
      (node (ref "ANT1") (pin "1") (pinfunction "1_1") (pintype "passive"))
      (node (ref "U2") (pin "1") (pinfunction "ANT_1") (pintype "passive"))
    )
    (net (code "19") (name "/SIR") (class "Default")
      (node (ref "F4") (pin "1") (pinfunction "1_1") (pintype "passive"))
      (node (ref "K2") (pin "3") (pinfunction "NO_3") (pintype "passive"))
    )
    (net (code "20") (name "/SIR_12V") (class "Default")
      (node (ref "F4") (pin "2") (pinfunction "2_2") (pintype "passive"))
      (node (ref "Q6") (pin "3") (pinfunction "E_3") (pintype "passive"))
      (node (ref "Q7") (pin "3") (pinfunction "E_3") (pintype "passive"))
      (node (ref "R29") (pin "1") (pinfunction "1_1") (pintype "passive"))
      (node (ref "R43") (pin "2") (pinfunction "2_2") (pintype "passive"))
      (node (ref "R44") (pin "1") (pinfunction "1_1") (pintype "passive"))
      (node (ref "U3") (pin "14") (pinfunction "VDD_14") (pintype "power_in"))
      (node (ref "X2") (pin "5") (pinfunction "5_5") (pintype "passive"))
    )
    (net (code "21") (name "/SRN+") (class "Default")
      (node (ref "Q7") (pin "2") (pinfunction "C_2") (pintype "passive"))
      (node (ref "Q9") (pin "2") (pinfunction "C_2") (pintype "passive"))
      (node (ref "X2") (pin "7") (pinfunction "7_7") (pintype "passive"))
    )
    (net (code "22") (name "/SRN-") (class "Default")
      (node (ref "Q6") (pin "2") (pinfunction "C_2") (pintype "passive"))
      (node (ref "Q8") (pin "2") (pinfunction "C_2") (pintype "passive"))
      (node (ref "X2") (pin "8") (pinfunction "8_8") (pintype "passive"))
    )
    (net (code "23") (name "/TX") (class "Default")
      (node (ref "P1") (pin "2") (pinfunction "2_2") (pintype "passive"))
      (node (ref "R8") (pin "1") (pinfunction "1_1") (pintype "passive"))
    )
    (net (code "24") (name "/Z1") (class "Default")
      (node (ref "R24") (pin "2") (pinfunction "2_2") (pintype "passive"))
      (node (ref "R25") (pin "1") (pinfunction "1_1") (pintype "passive"))
      (node (ref "X3") (pin "2") (pinfunction "2_2") (pintype "passive"))
    )
    (net (code "25") (name "/Z1+") (class "Default")
      (node (ref "F3") (pin "2") (pinfunction "2_2") (pintype "passive"))
      (node (ref "X2") (pin "3") (pinfunction "3_3") (pintype "passive"))
      (node (ref "X3") (pin "1") (pinfunction "1_1") (pintype "passive"))
      (node (ref "X3") (pin "3") (pinfunction "3_3") (pintype "passive"))
      (node (ref "X3") (pin "5") (pinfunction "5_5") (pintype "passive"))
      (node (ref "X3") (pin "7") (pinfunction "7_7") (pintype "passive"))
    )
    (net (code "26") (name "/Z1_PIN") (class "Default")
      (node (ref "IC1") (pin "4") (pinfunction "GPIO16/~{WAKE}_4") (pintype "passive"))
      (node (ref "R28") (pin "1") (pinfunction "1_1") (pintype "passive"))
    )
    (net (code "27") (name "/Z2") (class "Default")
      (node (ref "R46") (pin "2") (pinfunction "2_2") (pintype "passive"))
      (node (ref "R47") (pin "1") (pinfunction "1_1") (pintype "passive"))
      (node (ref "X3") (pin "4") (pinfunction "4_4") (pintype "passive"))
    )
    (net (code "28") (name "/Z2_PIN") (class "Default")
      (node (ref "IC1") (pin "5") (pinfunction "GPIO14/HSPICLK_5") (pintype "passive"))
      (node (ref "R50") (pin "1") (pinfunction "1_1") (pintype "passive"))
    )
    (net (code "29") (name "/Z3") (class "Default")
      (node (ref "R34") (pin "2") (pinfunction "2_2") (pintype "passive"))
      (node (ref "R35") (pin "1") (pinfunction "1_1") (pintype "passive"))
      (node (ref "X3") (pin "6") (pinfunction "6_6") (pintype "passive"))
    )
    (net (code "30") (name "/Z3_PIN") (class "Default")
      (node (ref "IC1") (pin "6") (pinfunction "GPIO12/HSPIQ_6") (pintype "passive"))
      (node (ref "R37") (pin "1") (pinfunction "1_1") (pintype "passive"))
    )
    (net (code "31") (name "/Z4") (class "Default")
      (node (ref "R51") (pin "2") (pinfunction "2_2") (pintype "passive"))
      (node (ref "R52") (pin "1") (pinfunction "1_1") (pintype "passive"))
      (node (ref "X3") (pin "8") (pinfunction "8_8") (pintype "passive"))
    )
    (net (code "32") (name "/Z4_PIN") (class "Default")
      (node (ref "IC1") (pin "7") (pinfunction "GPIO13/HSPID/CTS0/RXD2_7") (pintype "passive"))
      (node (ref "R53") (pin "1") (pinfunction "1_1") (pintype "passive"))
    )
    (net (code "33") (name "GND") (class "Default")
      (node (ref "ANT1") (pin "2") (pinfunction "2_2") (pintype "passive"))
      (node (ref "C1") (pin "2") (pinfunction "2_2") (pintype "passive"))
      (node (ref "C10") (pin "1") (pinfunction "1_1") (pintype "passive"))
      (node (ref "C11") (pin "1") (pinfunction "1_1") (pintype "passive"))
      (node (ref "C12") (pin "1") (pinfunction "1_1") (pintype "passive"))
      (node (ref "C13") (pin "2") (pinfunction "2_2") (pintype "passive"))
      (node (ref "C14") (pin "1") (pinfunction "1_1") (pintype "passive"))
      (node (ref "C16") (pin "2") (pinfunction "2_2") (pintype "passive"))
      (node (ref "C17") (pin "1") (pinfunction "1_1") (pintype "passive"))
      (node (ref "C18") (pin "1") (pinfunction "1_1") (pintype "passive"))
      (node (ref "C2") (pin "1") (pinfunction "1_1") (pintype "passive"))
      (node (ref "C21") (pin "1") (pinfunction "1_1") (pintype "passive"))
      (node (ref "C22") (pin "2") (pinfunction "2_2") (pintype "passive"))
      (node (ref "C23") (pin "1") (pinfunction "1_1") (pintype "passive"))
      (node (ref "C24") (pin "1") (pinfunction "1_1") (pintype "passive"))
      (node (ref "C25") (pin "2") (pinfunction "2_2") (pintype "passive"))
      (node (ref "C26") (pin "2") (pinfunction "2_2") (pintype "passive"))
      (node (ref "C27") (pin "2") (pinfunction "2_2") (pintype "passive"))
      (node (ref "C28") (pin "1") (pinfunction "1_1") (pintype "passive"))
      (node (ref "C29") (pin "1") (pinfunction "1_1") (pintype "passive"))
      (node (ref "C3") (pin "2") (pinfunction "2_2") (pintype "passive"))
      (node (ref "C30") (pin "1") (pinfunction "1_1") (pintype "passive"))
      (node (ref "C31") (pin "1") (pinfunction "1_1") (pintype "passive"))
      (node (ref "C32") (pin "1") (pinfunction "1_1") (pintype "passive"))
      (node (ref "C33") (pin "1") (pinfunction "1_1") (pintype "passive"))
      (node (ref "C34") (pin "1") (pinfunction "1_1") (pintype "passive"))
      (node (ref "C35") (pin "2") (pinfunction "2_2") (pintype "passive"))
      (node (ref "C36") (pin "2") (pinfunction "2_2") (pintype "passive"))
      (node (ref "C37") (pin "2") (pinfunction "2_2") (pintype "passive"))
      (node (ref "C38") (pin "2") (pinfunction "2_2") (pintype "passive"))
      (node (ref "C39") (pin "1") (pinfunction "1_1") (pintype "passive"))
      (node (ref "C4") (pin "2") (pinfunction "2_2") (pintype "passive"))
      (node (ref "C5") (pin "1") (pinfunction "1_1") (pintype "passive"))
      (node (ref "C6") (pin "1") (pinfunction "1_1") (pintype "passive"))
      (node (ref "C7") (pin "1") (pinfunction "1_1") (pintype "passive"))
      (node (ref "C8") (pin "2") (pinfunction "2_2") (pintype "passive"))
      (node (ref "C9") (pin "2") (pinfunction "2_2") (pintype "passive"))
      (node (ref "D1") (pin "1") (pinfunction "A_1") (pintype "passive"))
      (node (ref "D2") (pin "2") (pinfunction "CATHODE_2") (pintype "passive"))
      (node (ref "D4") (pin "2") (pintype "passive"))
      (node (ref "D8") (pin "1") (pinfunction "A_1") (pintype "passive"))
      (node (ref "DZ1") (pin "1") (pintype "passive"))
      (node (ref "DZ2") (pin "1") (pintype "passive"))
      (node (ref "DZ3") (pin "1") (pintype "passive"))
      (node (ref "DZ4") (pin "1") (pintype "passive"))
      (node (ref "DZ6") (pin "1") (pintype "passive"))
      (node (ref "DZ7") (pin "1") (pintype "passive"))
      (node (ref "DZ8") (pin "1") (pintype "passive"))
      (node (ref "IC1") (pin "15") (pinfunction "GND_15") (pintype "passive"))
      (node (ref "P3") (pin "1") (pinfunction "1_1") (pintype "passive"))
      (node (ref "P4") (pin "4") (pinfunction "4_4") (pintype "passive"))
      (node (ref "Q1") (pin "2") (pinfunction "E_2") (pintype "passive"))
      (node (ref "Q10") (pin "2") (pinfunction "E_2") (pintype "passive"))
      (node (ref "Q2") (pin "2") (pinfunction "E_2") (pintype "passive"))
      (node (ref "Q5") (pin "2") (pinfunction "E_2") (pintype "passive"))
      (node (ref "Q8") (pin "3") (pinfunction "E_3") (pintype "passive"))
      (node (ref "Q9") (pin "3") (pinfunction "E_3") (pintype "passive"))
      (node (ref "R10") (pin "2") (pinfunction "2_2") (pintype "passive"))
      (node (ref "R15") (pin "2") (pinfunction "2_2") (pintype "passive"))
      (node (ref "R19") (pin "2") (pinfunction "2_2") (pintype "passive"))
      (node (ref "R25") (pin "2") (pinfunction "2_2") (pintype "passive"))
      (node (ref "R3") (pin "1") (pinfunction "1_1") (pintype "passive"))
      (node (ref "R32") (pin "1") (pinfunction "1_1") (pintype "passive"))
      (node (ref "R35") (pin "2") (pinfunction "2_2") (pintype "passive"))
      (node (ref "R4") (pin "2") (pinfunction "2_2") (pintype "passive"))
      (node (ref "R45") (pin "1") (pinfunction "1_1") (pintype "passive"))
      (node (ref "R47") (pin "2") (pinfunction "2_2") (pintype "passive"))
      (node (ref "R48") (pin "1") (pinfunction "1_1") (pintype "passive"))
      (node (ref "R49") (pin "2") (pinfunction "2_2") (pintype "passive"))
      (node (ref "R52") (pin "2") (pinfunction "2_2") (pintype "passive"))
      (node (ref "R55") (pin "1") (pinfunction "1_1") (pintype "passive"))
      (node (ref "R7") (pin "2") (pinfunction "2_2") (pintype "passive"))
      (node (ref "U1") (pin "3") (pinfunction "GND_3") (pintype "power_in"))
      (node (ref "U1") (pin "6") (pinfunction "GND_6") (pintype "power_in"))
      (node (ref "U2") (pin "6") (pinfunction "GND_6") (pintype "power_in"))
      (node (ref "U5") (pin "1") (pinfunction "GND_1") (pintype "power_in"))
      (node (ref "VR1") (pin "1") (pinfunction "GND_1") (pintype "power_in"))
      (node (ref "VR2") (pin "3") (pinfunction "GROUND_3") (pintype "power_in"))
      (node (ref "VR2") (pin "5") (pinfunction "~{ON}/OFF_5") (pintype "input"))
      (node (ref "VR2") (pin "6") (pinfunction "GND_TAB_6") (pintype "power_in"))
      (node (ref "X1") (pin "1") (pinfunction "1_1") (pintype "passive"))
      (node (ref "X2") (pin "2") (pinfunction "2_2") (pintype "passive"))
      (node (ref "X2") (pin "4") (pinfunction "4_4") (pintype "passive"))
      (node (ref "X2") (pin "6") (pinfunction "6_6") (pintype "passive"))
    )
    (net (code "34") (name "Net-(C1-Pad1)") (class "Default")
      (node (ref "C1") (pin "1") (pinfunction "1_1") (pintype "passive"))
      (node (ref "C2") (pin "2") (pinfunction "2_2") (pintype "passive"))
      (node (ref "DP1") (pin "1") (pintype "passive"))
      (node (ref "L1") (pin "1") (pinfunction "1_1") (pintype "passive"))
      (node (ref "R1") (pin "1") (pinfunction "1_1") (pintype "passive"))
    )
    (net (code "35") (name "Net-(C15-Pad2)") (class "Default")
      (node (ref "C15") (pin "2") (pinfunction "2_2") (pintype "passive"))
      (node (ref "R16") (pin "2") (pinfunction "2_2") (pintype "passive"))
      (node (ref "R17") (pin "2") (pinfunction "2_2") (pintype "passive"))
      (node (ref "R20") (pin "1") (pinfunction "1_1") (pintype "passive"))
    )
    (net (code "36") (name "Net-(C18-Pad2)") (class "Default")
      (node (ref "C18") (pin "2") (pinfunction "2_2") (pintype "passive"))
      (node (ref "DZ3") (pin "2") (pintype "passive"))
      (node (ref "R18") (pin "1") (pinfunction "1_1") (pintype "passive"))
      (node (ref "R22") (pin "2") (pinfunction "2_2") (pintype "passive"))
    )
    (net (code "37") (name "Net-(C19-Pad2)") (class "Default")
      (node (ref "C19") (pin "2") (pinfunction "2_2") (pintype "passive"))
      (node (ref "R30") (pin "1") (pinfunction "1_1") (pintype "passive"))
    )
    (net (code "38") (name "Net-(C20-Pad2)") (class "Default")
      (node (ref "C20") (pin "2") (pinfunction "2_2") (pintype "passive"))
      (node (ref "R31") (pin "1") (pinfunction "1_1") (pintype "passive"))
    )
    (net (code "39") (name "Net-(C21-Pad2)") (class "Default")
      (node (ref "C21") (pin "2") (pinfunction "2_2") (pintype "passive"))
      (node (ref "DZ4") (pin "2") (pintype "passive"))
      (node (ref "R24") (pin "1") (pinfunction "1_1") (pintype "passive"))
      (node (ref "R28") (pin "2") (pinfunction "2_2") (pintype "passive"))
    )
    (net (code "40") (name "Net-(C24-Pad2)") (class "Default")
      (node (ref "C24") (pin "2") (pinfunction "2_2") (pintype "passive"))
      (node (ref "DZ6") (pin "2") (pintype "passive"))
      (node (ref "R34") (pin "1") (pinfunction "1_1") (pintype "passive"))
      (node (ref "R37") (pin "2") (pinfunction "2_2") (pintype "passive"))
    )
    (net (code "41") (name "Net-(C32-Pad2)") (class "Default")
      (node (ref "C32") (pin "2") (pinfunction "2_2") (pintype "passive"))
      (node (ref "DZ7") (pin "2") (pintype "passive"))
      (node (ref "R46") (pin "1") (pinfunction "1_1") (pintype "passive"))
      (node (ref "R50") (pin "2") (pinfunction "2_2") (pintype "passive"))
    )
    (net (code "42") (name "Net-(C39-Pad2)") (class "Default")
      (node (ref "C39") (pin "2") (pinfunction "2_2") (pintype "passive"))
      (node (ref "DZ8") (pin "2") (pintype "passive"))
      (node (ref "R51") (pin "1") (pinfunction "1_1") (pintype "passive"))
      (node (ref "R53") (pin "2") (pinfunction "2_2") (pintype "passive"))
    )
    (net (code "43") (name "Net-(D1-K)") (class "Default")
      (node (ref "D1") (pin "2") (pinfunction "K_2") (pintype "passive"))
      (node (ref "L1") (pin "2") (pinfunction "2_2") (pintype "passive"))
      (node (ref "U1") (pin "2") (pinfunction "OUT_2") (pintype "output"))
    )
    (net (code "44") (name "Net-(D2-ANODE)") (class "Default")
      (node (ref "D2") (pin "1") (pinfunction "ANODE_1") (pintype "passive"))
      (node (ref "R5") (pin "2") (pinfunction "2_2") (pintype "passive"))
    )
    (net (code "45") (name "Net-(D3-A)") (class "Default")
      (node (ref "D3") (pin "1") (pinfunction "A_1") (pintype "passive"))
      (node (ref "L2") (pin "2") (pinfunction "2_2") (pintype "passive"))
      (node (ref "VR1") (pin "3") (pinfunction "SW_3") (pintype "output"))
      (node (ref "VR1") (pin "6") (pinfunction "SW_6") (pintype "output"))
    )
    (net (code "46") (name "Net-(D3-K)") (class "Default")
      (node (ref "C22") (pin "1") (pinfunction "1_1") (pintype "passive"))
      (node (ref "C23") (pin "2") (pinfunction "2_2") (pintype "passive"))
      (node (ref "D3") (pin "2") (pinfunction "K_2") (pintype "passive"))
      (node (ref "D6") (pin "1") (pintype "passive"))
      (node (ref "R26") (pin "2") (pinfunction "2_2") (pintype "passive"))
    )
    (net (code "47") (name "Net-(D8-K)") (class "Default")
      (node (ref "D8") (pin "2") (pinfunction "K_2") (pintype "passive"))
      (node (ref "L3") (pin "2") (pinfunction "2_2") (pintype "passive"))
      (node (ref "VR2") (pin "2") (pinfunction "OUTPUT_2") (pintype "output"))
    )
    (net (code "48") (name "Net-(DP3-Pad2)") (class "Default")
      (node (ref "DP3") (pin "2") (pintype "passive"))
      (node (ref "DP4") (pin "1") (pintype "passive"))
    )
    (net (code "49") (name "Net-(DP4-Pad2)") (class "Default")
      (node (ref "DP4") (pin "2") (pintype "passive"))
      (node (ref "DP5") (pin "1") (pintype "passive"))
    )
    (net (code "50") (name "Net-(DZ5-Pad1)") (class "Default")
      (node (ref "DZ5") (pin "1") (pintype "passive"))
      (node (ref "R27") (pin "2") (pinfunction "2_2") (pintype "passive"))
    )
    (net (code "51") (name "Net-(F1-Pad2)") (class "Default")
      (node (ref "F1") (pin "2") (pinfunction "2_2") (pintype "passive"))
      (node (ref "X1") (pin "2") (pinfunction "2_2") (pintype "passive"))
    )
    (net (code "52") (name "Net-(F2-Pad2)") (class "Default")
      (node (ref "F2") (pin "2") (pinfunction "2_2") (pintype "passive"))
      (node (ref "X2") (pin "1") (pinfunction "1_1") (pintype "passive"))
    )
    (net (code "53") (name "Net-(K1-NO)") (class "Default")
      (node (ref "DP5") (pin "2") (pintype "passive"))
      (node (ref "K1") (pin "3") (pinfunction "NO_3") (pintype "passive"))
    )
    (net (code "54") (name "Net-(K1-T2)") (class "Default")
      (node (ref "D5") (pin "1") (pintype "passive"))
      (node (ref "K1") (pin "5") (pinfunction "T2_5") (pintype "passive"))
      (node (ref "Q2") (pin "3") (pinfunction "C_3") (pintype "passive"))
    )
    (net (code "55") (name "Net-(K2-T2)") (class "Default")
      (node (ref "D7") (pin "1") (pintype "passive"))
      (node (ref "K2") (pin "5") (pinfunction "T2_5") (pintype "passive"))
      (node (ref "Q10") (pin "3") (pinfunction "C_3") (pintype "passive"))
    )
    (net (code "56") (name "Net-(Q1-B)") (class "Default")
      (node (ref "Q1") (pin "1") (pinfunction "B_1") (pintype "passive"))
      (node (ref "R4") (pin "1") (pinfunction "1_1") (pintype "passive"))
      (node (ref "R6") (pin "1") (pinfunction "1_1") (pintype "passive"))
    )
    (net (code "57") (name "Net-(Q1-C)") (class "Default")
      (node (ref "Q1") (pin "3") (pinfunction "C_3") (pintype "passive"))
      (node (ref "U2") (pin "3") (pinfunction "RST_3") (pintype "passive"))
    )
    (net (code "58") (name "Net-(Q2-B)") (class "Default")
      (node (ref "Q2") (pin "1") (pinfunction "B_1") (pintype "passive"))
      (node (ref "R27") (pin "1") (pinfunction "1_1") (pintype "passive"))
    )
    (net (code "59") (name "Net-(Q3-B)") (class "Default")
      (node (ref "Q3") (pin "2") (pinfunction "B_2") (pintype "passive"))
      (node (ref "R38") (pin "2") (pinfunction "2_2") (pintype "passive"))
    )
    (net (code "60") (name "Net-(Q3-C)") (class "Default")
      (node (ref "Q3") (pin "1") (pinfunction "C_1") (pintype "passive"))
      (node (ref "R41") (pin "2") (pinfunction "2_2") (pintype "passive"))
    )
    (net (code "61") (name "Net-(Q3-E)") (class "Default")
      (node (ref "Q3") (pin "3") (pinfunction "E_3") (pintype "passive"))
      (node (ref "Q9") (pin "1") (pinfunction "B_1") (pintype "passive"))
      (node (ref "R48") (pin "2") (pinfunction "2_2") (pintype "passive"))
    )
    (net (code "62") (name "Net-(Q4-B)") (class "Default")
      (node (ref "Q4") (pin "2") (pinfunction "B_2") (pintype "passive"))
      (node (ref "R39") (pin "2") (pinfunction "2_2") (pintype "passive"))
    )
    (net (code "63") (name "Net-(Q4-C)") (class "Default")
      (node (ref "Q4") (pin "1") (pinfunction "C_1") (pintype "passive"))
      (node (ref "R42") (pin "2") (pinfunction "2_2") (pintype "passive"))
    )
    (net (code "64") (name "Net-(Q4-E)") (class "Default")
      (node (ref "Q4") (pin "3") (pinfunction "E_3") (pintype "passive"))
      (node (ref "Q8") (pin "1") (pinfunction "B_1") (pintype "passive"))
      (node (ref "R49") (pin "1") (pinfunction "1_1") (pintype "passive"))
    )
    (net (code "65") (name "Net-(Q5-B)") (class "Default")
      (node (ref "Q5") (pin "1") (pinfunction "B_1") (pintype "passive"))
      (node (ref "R40") (pin "1") (pinfunction "1_1") (pintype "passive"))
      (node (ref "R45") (pin "2") (pinfunction "2_2") (pintype "passive"))
    )
    (net (code "66") (name "Net-(Q5-C)") (class "Default")
      (node (ref "Q5") (pin "3") (pinfunction "C_3") (pintype "passive"))
      (node (ref "SP1") (pin "2") (pinfunction "-_2") (pintype "passive"))
    )
    (net (code "67") (name "Net-(Q6-B)") (class "Default")
      (node (ref "Q6") (pin "1") (pinfunction "B_1") (pintype "passive"))
      (node (ref "R41") (pin "1") (pinfunction "1_1") (pintype "passive"))
      (node (ref "R43") (pin "1") (pinfunction "1_1") (pintype "passive"))
    )
    (net (code "68") (name "Net-(Q7-B)") (class "Default")
      (node (ref "Q7") (pin "1") (pinfunction "B_1") (pintype "passive"))
      (node (ref "R42") (pin "1") (pinfunction "1_1") (pintype "passive"))
      (node (ref "R44") (pin "2") (pinfunction "2_2") (pintype "passive"))
    )
    (net (code "69") (name "Net-(Q10-B)") (class "Default")
      (node (ref "Q10") (pin "1") (pinfunction "B_1") (pintype "passive"))
      (node (ref "R54") (pin "1") (pinfunction "1_1") (pintype "passive"))
      (node (ref "R55") (pin "2") (pinfunction "2_2") (pintype "passive"))
    )
    (net (code "70") (name "Net-(R20-Pad2)") (class "Default")
      (node (ref "R20") (pin "2") (pinfunction "2_2") (pintype "passive"))
      (node (ref "R21") (pin "1") (pinfunction "1_1") (pintype "passive"))
      (node (ref "R23") (pin "1") (pinfunction "1_1") (pintype "passive"))
      (node (ref "R29") (pin "2") (pinfunction "2_2") (pintype "passive"))
    )
    (net (code "71") (name "Net-(U1-FB)") (class "Default")
      (node (ref "R1") (pin "2") (pinfunction "2_2") (pintype "passive"))
      (node (ref "R3") (pin "2") (pinfunction "2_2") (pintype "passive"))
      (node (ref "U1") (pin "4") (pinfunction "FB_4") (pintype "input"))
    )
    (net (code "72") (name "Net-(U1-~{ON!{slash}OFF})") (class "Default")
      (node (ref "R2") (pin "2") (pinfunction "2_2") (pintype "passive"))
      (node (ref "U1") (pin "5") (pinfunction "~{ON!/OFF}_5") (pintype "input"))
    )
    (net (code "73") (name "Net-(U2-RXD)") (class "Default")
      (node (ref "R10") (pin "1") (pinfunction "1_1") (pintype "passive"))
      (node (ref "R8") (pin "2") (pinfunction "2_2") (pintype "passive"))
      (node (ref "U2") (pin "4") (pinfunction "RXD_4") (pintype "passive"))
    )
    (net (code "74") (name "Net-(U2-TXD)") (class "Default")
      (node (ref "R9") (pin "2") (pinfunction "2_2") (pintype "passive"))
      (node (ref "U2") (pin "5") (pinfunction "TXD_5") (pintype "passive"))
    )
    (net (code "75") (name "Net-(U2-VCC)") (class "Default")
      (node (ref "C6") (pin "2") (pinfunction "2_2") (pintype "passive"))
      (node (ref "C7") (pin "2") (pinfunction "2_2") (pintype "passive"))
      (node (ref "C8") (pin "1") (pinfunction "1_1") (pintype "passive"))
      (node (ref "C9") (pin "1") (pinfunction "1_1") (pintype "passive"))
      (node (ref "DP1") (pin "2") (pintype "passive"))
      (node (ref "DZ2") (pin "2") (pintype "passive"))
      (node (ref "U2") (pin "2") (pinfunction "VCC_2") (pintype "power_in"))
    )
    (net (code "76") (name "Net-(U3-A)") (class "Default")
      (node (ref "R16") (pin "1") (pinfunction "1_1") (pintype "passive"))
      (node (ref "U3") (pin "1") (pinfunction "A_1") (pintype "input"))
      (node (ref "U3") (pin "2") (pinfunction "B_2") (pintype "input"))
      (node (ref "U3") (pin "4") (pinfunction "K_4") (pintype "output"))
    )
    (net (code "77") (name "Net-(U3-C)") (class "Default")
      (node (ref "R17") (pin "1") (pinfunction "1_1") (pintype "passive"))
      (node (ref "U3") (pin "5") (pinfunction "C_5") (pintype "input"))
      (node (ref "U3") (pin "6") (pinfunction "D_6") (pintype "input"))
    )
    (net (code "78") (name "Net-(U3-E)") (class "Default")
      (node (ref "C19") (pin "1") (pinfunction "1_1") (pintype "passive"))
      (node (ref "R21") (pin "2") (pinfunction "2_2") (pintype "passive"))
      (node (ref "U3") (pin "8") (pinfunction "E_8") (pintype "input"))
      (node (ref "U3") (pin "9") (pinfunction "F_9") (pintype "input"))
    )
    (net (code "79") (name "Net-(U3-G)") (class "Default")
      (node (ref "C20") (pin "1") (pinfunction "1_1") (pintype "passive"))
      (node (ref "R23") (pin "2") (pinfunction "2_2") (pintype "passive"))
      (node (ref "U3") (pin "12") (pinfunction "G_12") (pintype "input"))
      (node (ref "U3") (pin "13") (pinfunction "H_13") (pintype "input"))
    )
    (net (code "80") (name "Net-(U3-J)") (class "Default")
      (node (ref "C15") (pin "1") (pinfunction "1_1") (pintype "passive"))
      (node (ref "U3") (pin "3") (pinfunction "J_3") (pintype "output"))
    )
    (net (code "81") (name "Net-(U3-L)") (class "Default")
      (node (ref "R31") (pin "2") (pinfunction "2_2") (pintype "passive"))
      (node (ref "R38") (pin "1") (pinfunction "1_1") (pintype "passive"))
      (node (ref "U3") (pin "10") (pinfunction "L_10") (pintype "output"))
    )
    (net (code "82") (name "Net-(U3-M)") (class "Default")
      (node (ref "R30") (pin "2") (pinfunction "2_2") (pintype "passive"))
      (node (ref "R39") (pin "1") (pinfunction "1_1") (pintype "passive"))
      (node (ref "U3") (pin "11") (pinfunction "M_11") (pintype "output"))
    )
    (net (code "83") (name "Net-(U3-VSS)") (class "Default")
      (node (ref "D4") (pin "1") (pintype "passive"))
      (node (ref "U3") (pin "7") (pinfunction "VSS_7") (pintype "power_in"))
    )
    (net (code "84") (name "Net-(U4-VIN)") (class "Default")
      (node (ref "C25") (pin "1") (pinfunction "1_1") (pintype "passive"))
      (node (ref "D6") (pin "2") (pintype "passive"))
      (node (ref "U4") (pin "3") (pinfunction "VIN_3") (pintype "input"))
    )
    (net (code "85") (name "Net-(U4-VOUT)") (class "Default")
      (node (ref "R33") (pin "1") (pinfunction "1_1") (pintype "passive"))
      (node (ref "R36") (pin "1") (pinfunction "1_1") (pintype "passive"))
      (node (ref "U4") (pin "2") (pinfunction "VOUT_2") (pintype "output"))
    )
    (net (code "86") (name "Net-(VR1-FB)") (class "Default")
      (node (ref "R26") (pin "1") (pinfunction "1_1") (pintype "passive"))
      (node (ref "R32") (pin "2") (pinfunction "2_2") (pintype "passive"))
      (node (ref "VR1") (pin "5") (pinfunction "FB_5") (pintype "input"))
    )
    (net (code "87") (name "unconnected-(IC1-GPIO9{slash}SD_D2-Pad11)") (class "Default")
      (node (ref "IC1") (pin "11") (pinfunction "GPIO9/SD_D2_11") (pintype "passive"))
    )
    (net (code "88") (name "unconnected-(IC1-SPI_CLK{slash}SD_CLK-Pad14)") (class "Default")
      (node (ref "IC1") (pin "14") (pinfunction "SPI_CLK/SD_CLK_14") (pintype "passive"))
    )
    (net (code "89") (name "unconnected-(IC1-SPI_INT{slash}SD_D1-Pad13)") (class "Default")
      (node (ref "IC1") (pin "13") (pinfunction "SPI_INT/SD_D1_13") (pintype "passive"))
    )
    (net (code "90") (name "unconnected-(IC1-SPI_MISO{slash}SD_D0-Pad10)") (class "Default")
      (node (ref "IC1") (pin "10") (pinfunction "SPI_MISO/SD_D0_10") (pintype "passive"))
    )
    (net (code "91") (name "unconnected-(IC1-SPI_MOSI{slash}SD_CMD-Pad9)") (class "Default")
      (node (ref "IC1") (pin "9") (pinfunction "SPI_MOSI/SD_CMD_9") (pintype "passive"))
    )
    (net (code "92") (name "unconnected-(K1-NC-Pad2)") (class "Default")
      (node (ref "K1") (pin "2") (pinfunction "NC_2") (pintype "passive"))
    )
    (net (code "93") (name "unconnected-(K2-NC-Pad2)") (class "Default")
      (node (ref "K2") (pin "2") (pinfunction "NC_2") (pintype "passive"))
    )
    (net (code "94") (name "unconnected-(P4-Pad3)") (class "Default")
      (node (ref "P4") (pin "3") (pinfunction "3_3") (pintype "passive"))
    )
    (net (code "95") (name "unconnected-(U2-DTR-Pad11)") (class "Default")
      (node (ref "U2") (pin "11") (pinfunction "DTR_11") (pintype "passive"))
    )
    (net (code "96") (name "unconnected-(U2-MICN-Pad9)") (class "Default")
      (node (ref "U2") (pin "9") (pinfunction "MICN_9") (pintype "passive"))
    )
    (net (code "97") (name "unconnected-(U2-MICP-Pad10)") (class "Default")
      (node (ref "U2") (pin "10") (pinfunction "MICP_10") (pintype "passive"))
    )
    (net (code "98") (name "unconnected-(U2-RING-Pad12)") (class "Default")
      (node (ref "U2") (pin "12") (pinfunction "RING_12") (pintype "passive"))
    )
    (net (code "99") (name "unconnected-(U2-SPKN-Pad7)") (class "Default")
      (node (ref "U2") (pin "7") (pinfunction "SPKN_7") (pintype "passive"))
    )
    (net (code "100") (name "unconnected-(U2-SPKP-Pad8)") (class "Default")
      (node (ref "U2") (pin "8") (pinfunction "SPKP_8") (pintype "passive"))
    )
    (net (code "101") (name "unconnected-(VR1-EN-Pad2)") (class "Default")
      (node (ref "VR1") (pin "2") (pinfunction "EN_2") (pintype "input"))
    )
  )
)
